# FY_-_OPTO_BOARD_3_GEN.net
KiCad netlist of a schematic drawn in EAGLE
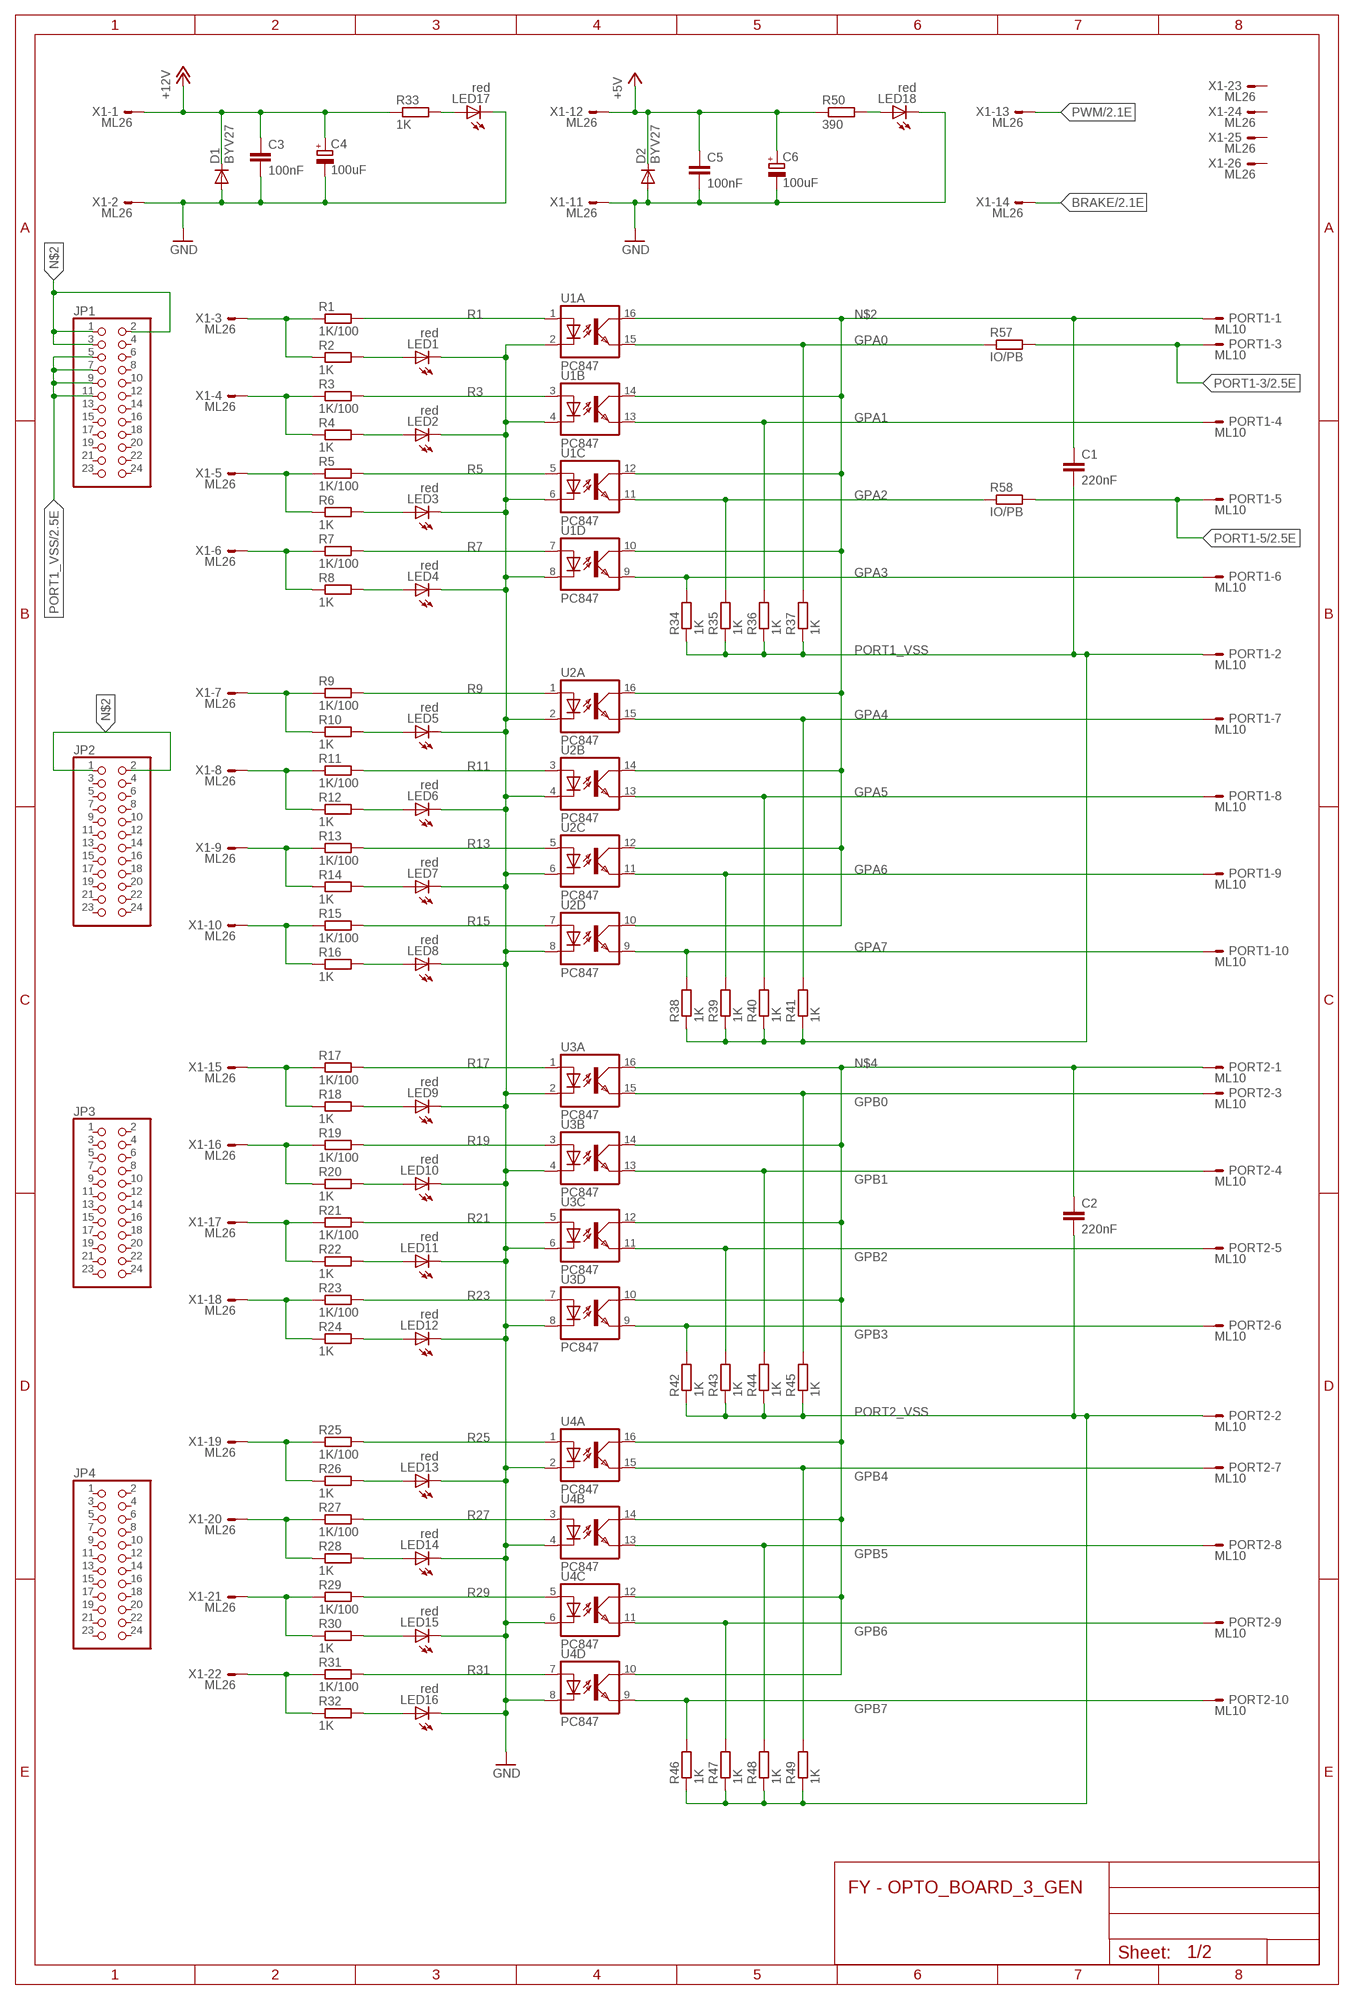
[diagram p0: schematic, sheet 1]
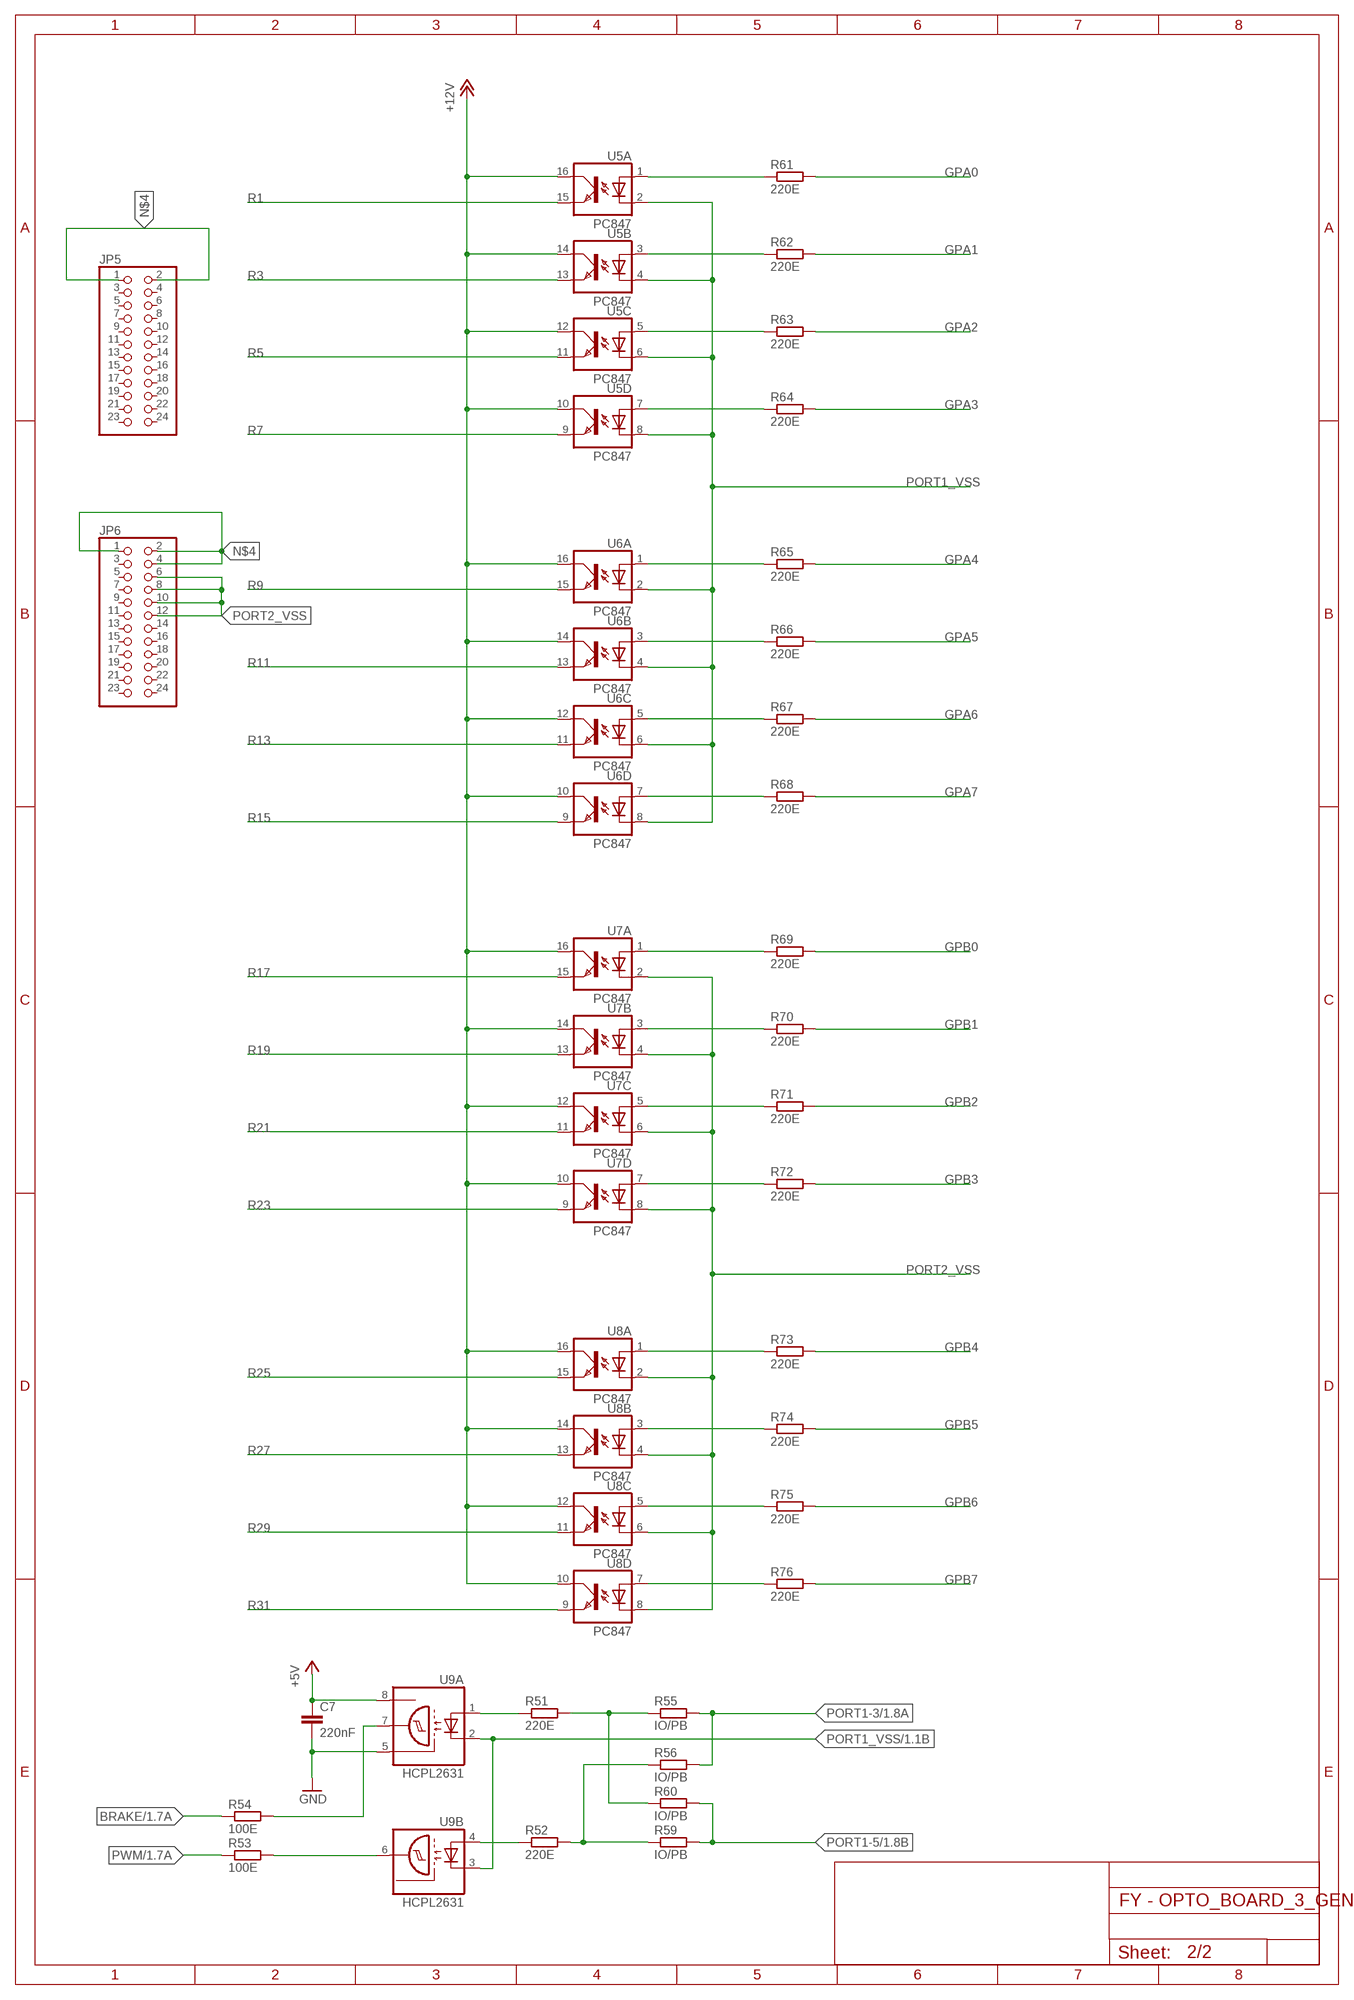
[diagram p1: schematic, sheet 2]

(export (version "E")
  (design (tool "Eeschema 10.0.6"))
  (components
    (comp (ref "C1")
      (value "220nF")
      (footprint "eagle-import:C050-025X075")
      (libsource (lib "eagle-import") (part "C-EU050-025X075"))
    )
    (comp (ref "C2")
      (value "220nF")
      (footprint "eagle-import:C050-025X075")
      (libsource (lib "eagle-import") (part "C-EU050-025X075"))
    )
    (comp (ref "C3")
      (value "100nF")
      (footprint "eagle-import:C050-025X075")
      (libsource (lib "eagle-import") (part "C-EU050-025X075"))
    )
    (comp (ref "C4")
      (value "100uF")
      (footprint "eagle-import:E5-8,5")
      (libsource (lib "eagle-import") (part "CPOL-EUE5-8.5"))
    )
    (comp (ref "C5")
      (value "100nF")
      (footprint "eagle-import:C050-025X075")
      (libsource (lib "eagle-import") (part "C-EU050-025X075"))
    )
    (comp (ref "C6")
      (value "100uF")
      (footprint "eagle-import:E5-8,5")
      (libsource (lib "eagle-import") (part "CPOL-EUE5-8.5"))
    )
    (comp (ref "D1")
      (value "BYV27")
      (footprint "eagle-import:SOD57-10")
      (libsource (lib "eagle-import") (part "BYV27"))
    )
    (comp (ref "D2")
      (value "BYV27")
      (footprint "eagle-import:SOD57-10")
      (libsource (lib "eagle-import") (part "BYV27"))
    )
    (comp (ref "JP1")
      (value "PINHD-2X12")
      (footprint "eagle-import:2X12")
      (libsource (lib "eagle-import") (part "PINHD-2X12"))
    )
    (comp (ref "JP2")
      (value "PINHD-2X12")
      (footprint "eagle-import:2X12")
      (libsource (lib "eagle-import") (part "PINHD-2X12"))
    )
    (comp (ref "JP3")
      (value "PINHD-2X12")
      (footprint "eagle-import:2X12")
      (libsource (lib "eagle-import") (part "PINHD-2X12"))
    )
    (comp (ref "JP4")
      (value "PINHD-2X12")
      (footprint "eagle-import:2X12")
      (libsource (lib "eagle-import") (part "PINHD-2X12"))
    )
    (comp (ref "LED1")
      (value "red")
      (footprint "eagle-import:LED3MM")
      (libsource (lib "eagle-import") (part "LED3MM"))
    )
    (comp (ref "LED2")
      (value "red")
      (footprint "eagle-import:LED3MM")
      (libsource (lib "eagle-import") (part "LED3MM"))
    )
    (comp (ref "LED3")
      (value "red")
      (footprint "eagle-import:LED3MM")
      (libsource (lib "eagle-import") (part "LED3MM"))
    )
    (comp (ref "LED4")
      (value "red")
      (footprint "eagle-import:LED3MM")
      (libsource (lib "eagle-import") (part "LED3MM"))
    )
    (comp (ref "LED5")
      (value "red")
      (footprint "eagle-import:LED3MM")
      (libsource (lib "eagle-import") (part "LED3MM"))
    )
    (comp (ref "LED6")
      (value "red")
      (footprint "eagle-import:LED3MM")
      (libsource (lib "eagle-import") (part "LED3MM"))
    )
    (comp (ref "LED7")
      (value "red")
      (footprint "eagle-import:LED3MM")
      (libsource (lib "eagle-import") (part "LED3MM"))
    )
    (comp (ref "LED8")
      (value "red")
      (footprint "eagle-import:LED3MM")
      (libsource (lib "eagle-import") (part "LED3MM"))
    )
    (comp (ref "LED9")
      (value "red")
      (footprint "eagle-import:LED3MM")
      (libsource (lib "eagle-import") (part "LED3MM"))
    )
    (comp (ref "LED10")
      (value "red")
      (footprint "eagle-import:LED3MM")
      (libsource (lib "eagle-import") (part "LED3MM"))
    )
    (comp (ref "LED11")
      (value "red")
      (footprint "eagle-import:LED3MM")
      (libsource (lib "eagle-import") (part "LED3MM"))
    )
    (comp (ref "LED12")
      (value "red")
      (footprint "eagle-import:LED3MM")
      (libsource (lib "eagle-import") (part "LED3MM"))
    )
    (comp (ref "LED13")
      (value "red")
      (footprint "eagle-import:LED3MM")
      (libsource (lib "eagle-import") (part "LED3MM"))
    )
    (comp (ref "LED14")
      (value "red")
      (footprint "eagle-import:LED3MM")
      (libsource (lib "eagle-import") (part "LED3MM"))
    )
    (comp (ref "LED15")
      (value "red")
      (footprint "eagle-import:LED3MM")
      (libsource (lib "eagle-import") (part "LED3MM"))
    )
    (comp (ref "LED16")
      (value "red")
      (footprint "eagle-import:LED3MM")
      (libsource (lib "eagle-import") (part "LED3MM"))
    )
    (comp (ref "LED17")
      (value "red")
      (footprint "eagle-import:LED3MM")
      (libsource (lib "eagle-import") (part "LED3MM"))
    )
    (comp (ref "LED18")
      (value "red")
      (footprint "eagle-import:LED3MM")
      (libsource (lib "eagle-import") (part "LED3MM"))
    )
    (comp (ref "PORT1")
      (value "ML10")
      (footprint "eagle-import:ML10")
      (libsource (lib "eagle-import") (part "ML10?E"))
    )
    (comp (ref "PORT2")
      (value "ML10")
      (footprint "eagle-import:ML10")
      (libsource (lib "eagle-import") (part "ML10?E"))
    )
    (comp (ref "R1")
      (value "1K/100")
      (footprint "eagle-import:0207_10")
      (libsource (lib "eagle-import") (part "R-EU_0207/10"))
    )
    (comp (ref "R2")
      (value "1K")
      (footprint "eagle-import:0207_10")
      (libsource (lib "eagle-import") (part "R-EU_0207/10"))
    )
    (comp (ref "R3")
      (value "1K/100")
      (footprint "eagle-import:0207_10")
      (libsource (lib "eagle-import") (part "R-EU_0207/10"))
    )
    (comp (ref "R4")
      (value "1K")
      (footprint "eagle-import:0207_10")
      (libsource (lib "eagle-import") (part "R-EU_0207/10"))
    )
    (comp (ref "R5")
      (value "1K/100")
      (footprint "eagle-import:0207_10")
      (libsource (lib "eagle-import") (part "R-EU_0207/10"))
    )
    (comp (ref "R6")
      (value "1K")
      (footprint "eagle-import:0207_10")
      (libsource (lib "eagle-import") (part "R-EU_0207/10"))
    )
    (comp (ref "R7")
      (value "1K/100")
      (footprint "eagle-import:0207_10")
      (libsource (lib "eagle-import") (part "R-EU_0207/10"))
    )
    (comp (ref "R8")
      (value "1K")
      (footprint "eagle-import:0207_10")
      (libsource (lib "eagle-import") (part "R-EU_0207/10"))
    )
    (comp (ref "R9")
      (value "1K/100")
      (footprint "eagle-import:0207_10")
      (libsource (lib "eagle-import") (part "R-EU_0207/10"))
    )
    (comp (ref "R10")
      (value "1K")
      (footprint "eagle-import:0207_10")
      (libsource (lib "eagle-import") (part "R-EU_0207/10"))
    )
    (comp (ref "R11")
      (value "1K/100")
      (footprint "eagle-import:0207_10")
      (libsource (lib "eagle-import") (part "R-EU_0207/10"))
    )
    (comp (ref "R12")
      (value "1K")
      (footprint "eagle-import:0207_10")
      (libsource (lib "eagle-import") (part "R-EU_0207/10"))
    )
    (comp (ref "R13")
      (value "1K/100")
      (footprint "eagle-import:0207_10")
      (libsource (lib "eagle-import") (part "R-EU_0207/10"))
    )
    (comp (ref "R14")
      (value "1K")
      (footprint "eagle-import:0207_10")
      (libsource (lib "eagle-import") (part "R-EU_0207/10"))
    )
    (comp (ref "R15")
      (value "1K/100")
      (footprint "eagle-import:0207_10")
      (libsource (lib "eagle-import") (part "R-EU_0207/10"))
    )
    (comp (ref "R16")
      (value "1K")
      (footprint "eagle-import:0207_10")
      (libsource (lib "eagle-import") (part "R-EU_0207/10"))
    )
    (comp (ref "R17")
      (value "1K/100")
      (footprint "eagle-import:0207_10")
      (libsource (lib "eagle-import") (part "R-EU_0207/10"))
    )
    (comp (ref "R18")
      (value "1K")
      (footprint "eagle-import:0207_10")
      (libsource (lib "eagle-import") (part "R-EU_0207/10"))
    )
    (comp (ref "R19")
      (value "1K/100")
      (footprint "eagle-import:0207_10")
      (libsource (lib "eagle-import") (part "R-EU_0207/10"))
    )
    (comp (ref "R20")
      (value "1K")
      (footprint "eagle-import:0207_10")
      (libsource (lib "eagle-import") (part "R-EU_0207/10"))
    )
    (comp (ref "R21")
      (value "1K/100")
      (footprint "eagle-import:0207_10")
      (libsource (lib "eagle-import") (part "R-EU_0207/10"))
    )
    (comp (ref "R22")
      (value "1K")
      (footprint "eagle-import:0207_10")
      (libsource (lib "eagle-import") (part "R-EU_0207/10"))
    )
    (comp (ref "R23")
      (value "1K/100")
      (footprint "eagle-import:0207_10")
      (libsource (lib "eagle-import") (part "R-EU_0207/10"))
    )
    (comp (ref "R24")
      (value "1K")
      (footprint "eagle-import:0207_10")
      (libsource (lib "eagle-import") (part "R-EU_0207/10"))
    )
    (comp (ref "R25")
      (value "1K/100")
      (footprint "eagle-import:0207_10")
      (libsource (lib "eagle-import") (part "R-EU_0207/10"))
    )
    (comp (ref "R26")
      (value "1K")
      (footprint "eagle-import:0207_10")
      (libsource (lib "eagle-import") (part "R-EU_0207/10"))
    )
    (comp (ref "R27")
      (value "1K/100")
      (footprint "eagle-import:0207_10")
      (libsource (lib "eagle-import") (part "R-EU_0207/10"))
    )
    (comp (ref "R28")
      (value "1K")
      (footprint "eagle-import:0207_10")
      (libsource (lib "eagle-import") (part "R-EU_0207/10"))
    )
    (comp (ref "R29")
      (value "1K/100")
      (footprint "eagle-import:0207_10")
      (libsource (lib "eagle-import") (part "R-EU_0207/10"))
    )
    (comp (ref "R30")
      (value "1K")
      (footprint "eagle-import:0207_10")
      (libsource (lib "eagle-import") (part "R-EU_0207/10"))
    )
    (comp (ref "R31")
      (value "1K/100")
      (footprint "eagle-import:0207_10")
      (libsource (lib "eagle-import") (part "R-EU_0207/10"))
    )
    (comp (ref "R32")
      (value "1K")
      (footprint "eagle-import:0207_10")
      (libsource (lib "eagle-import") (part "R-EU_0207/10"))
    )
    (comp (ref "R33")
      (value "1K")
      (footprint "eagle-import:0207_10")
      (libsource (lib "eagle-import") (part "R-EU_0207/10"))
    )
    (comp (ref "R34")
      (value "1K")
      (footprint "eagle-import:0207_10")
      (libsource (lib "eagle-import") (part "R-EU_0207/10"))
    )
    (comp (ref "R35")
      (value "1K")
      (footprint "eagle-import:0207_10")
      (libsource (lib "eagle-import") (part "R-EU_0207/10"))
    )
    (comp (ref "R36")
      (value "1K")
      (footprint "eagle-import:0207_10")
      (libsource (lib "eagle-import") (part "R-EU_0207/10"))
    )
    (comp (ref "R37")
      (value "1K")
      (footprint "eagle-import:0207_10")
      (libsource (lib "eagle-import") (part "R-EU_0207/10"))
    )
    (comp (ref "R38")
      (value "1K")
      (footprint "eagle-import:0207_10")
      (libsource (lib "eagle-import") (part "R-EU_0207/10"))
    )
    (comp (ref "R39")
      (value "1K")
      (footprint "eagle-import:0207_10")
      (libsource (lib "eagle-import") (part "R-EU_0207/10"))
    )
    (comp (ref "R40")
      (value "1K")
      (footprint "eagle-import:0207_10")
      (libsource (lib "eagle-import") (part "R-EU_0207/10"))
    )
    (comp (ref "R41")
      (value "1K")
      (footprint "eagle-import:0207_10")
      (libsource (lib "eagle-import") (part "R-EU_0207/10"))
    )
    (comp (ref "R42")
      (value "1K")
      (footprint "eagle-import:0207_10")
      (libsource (lib "eagle-import") (part "R-EU_0207/10"))
    )
    (comp (ref "R43")
      (value "1K")
      (footprint "eagle-import:0207_10")
      (libsource (lib "eagle-import") (part "R-EU_0207/10"))
    )
    (comp (ref "R44")
      (value "1K")
      (footprint "eagle-import:0207_10")
      (libsource (lib "eagle-import") (part "R-EU_0207/10"))
    )
    (comp (ref "R45")
      (value "1K")
      (footprint "eagle-import:0207_10")
      (libsource (lib "eagle-import") (part "R-EU_0207/10"))
    )
    (comp (ref "R46")
      (value "1K")
      (footprint "eagle-import:0207_10")
      (libsource (lib "eagle-import") (part "R-EU_0207/10"))
    )
    (comp (ref "R47")
      (value "1K")
      (footprint "eagle-import:0207_10")
      (libsource (lib "eagle-import") (part "R-EU_0207/10"))
    )
    (comp (ref "R48")
      (value "1K")
      (footprint "eagle-import:0207_10")
      (libsource (lib "eagle-import") (part "R-EU_0207/10"))
    )
    (comp (ref "R49")
      (value "1K")
      (footprint "eagle-import:0207_10")
      (libsource (lib "eagle-import") (part "R-EU_0207/10"))
    )
    (comp (ref "R50")
      (value "390")
      (footprint "eagle-import:0207_10")
      (libsource (lib "eagle-import") (part "R-EU_0207/10"))
    )
    (comp (ref "R57")
      (value "IO/PB")
      (footprint "eagle-import:0204V")
      (libsource (lib "eagle-import") (part "R-EU_0204/2V"))
    )
    (comp (ref "R58")
      (value "IO/PB")
      (footprint "eagle-import:0204V")
      (libsource (lib "eagle-import") (part "R-EU_0204/2V"))
    )
    (comp (ref "U1")
      (value "PC847")
      (footprint "eagle-import:DIL16")
      (libsource (lib "eagle-import") (part "PC847"))
    )
    (comp (ref "U2")
      (value "PC847")
      (footprint "eagle-import:DIL16")
      (libsource (lib "eagle-import") (part "PC847"))
    )
    (comp (ref "U3")
      (value "PC847")
      (footprint "eagle-import:DIL16")
      (libsource (lib "eagle-import") (part "PC847"))
    )
    (comp (ref "U4")
      (value "PC847")
      (footprint "eagle-import:DIL16")
      (libsource (lib "eagle-import") (part "PC847"))
    )
    (comp (ref "X1")
      (value "ML26")
      (footprint "eagle-import:ML26")
      (libsource (lib "eagle-import") (part "ML26?E"))
    )
    (comp (ref "C7")
      (value "220nF")
      (footprint "eagle-import:C050-025X075")
      (libsource (lib "eagle-import") (part "C-EU050-025X075"))
    )
    (comp (ref "JP5")
      (value "PINHD-2X12")
      (footprint "eagle-import:2X12")
      (libsource (lib "eagle-import") (part "PINHD-2X12"))
    )
    (comp (ref "JP6")
      (value "PINHD-2X12")
      (footprint "eagle-import:2X12")
      (libsource (lib "eagle-import") (part "PINHD-2X12"))
    )
    (comp (ref "R51")
      (value "220E")
      (footprint "eagle-import:0207_10")
      (libsource (lib "eagle-import") (part "R-EU_0207/10"))
    )
    (comp (ref "R52")
      (value "220E")
      (footprint "eagle-import:0207_10")
      (libsource (lib "eagle-import") (part "R-EU_0207/10"))
    )
    (comp (ref "R53")
      (value "100E")
      (footprint "eagle-import:0207_10")
      (libsource (lib "eagle-import") (part "R-EU_0207/10"))
    )
    (comp (ref "R54")
      (value "100E")
      (footprint "eagle-import:0207_10")
      (libsource (lib "eagle-import") (part "R-EU_0207/10"))
    )
    (comp (ref "R55")
      (value "IO/PB")
      (footprint "eagle-import:0204V")
      (libsource (lib "eagle-import") (part "R-EU_0204/2V"))
    )
    (comp (ref "R56")
      (value "IO/PB")
      (footprint "eagle-import:0204V")
      (libsource (lib "eagle-import") (part "R-EU_0204/2V"))
    )
    (comp (ref "R59")
      (value "IO/PB")
      (footprint "eagle-import:0204V")
      (libsource (lib "eagle-import") (part "R-EU_0204/2V"))
    )
    (comp (ref "R60")
      (value "IO/PB")
      (footprint "eagle-import:0204V")
      (libsource (lib "eagle-import") (part "R-EU_0204/2V"))
    )
    (comp (ref "R61")
      (value "220E")
      (footprint "eagle-import:0207_10")
      (libsource (lib "eagle-import") (part "R-EU_0207/10"))
    )
    (comp (ref "R62")
      (value "220E")
      (footprint "eagle-import:0207_10")
      (libsource (lib "eagle-import") (part "R-EU_0207/10"))
    )
    (comp (ref "R63")
      (value "220E")
      (footprint "eagle-import:0207_10")
      (libsource (lib "eagle-import") (part "R-EU_0207/10"))
    )
    (comp (ref "R64")
      (value "220E")
      (footprint "eagle-import:0207_10")
      (libsource (lib "eagle-import") (part "R-EU_0207/10"))
    )
    (comp (ref "R65")
      (value "220E")
      (footprint "eagle-import:0207_10")
      (libsource (lib "eagle-import") (part "R-EU_0207/10"))
    )
    (comp (ref "R66")
      (value "220E")
      (footprint "eagle-import:0207_10")
      (libsource (lib "eagle-import") (part "R-EU_0207/10"))
    )
    (comp (ref "R67")
      (value "220E")
      (footprint "eagle-import:0207_10")
      (libsource (lib "eagle-import") (part "R-EU_0207/10"))
    )
    (comp (ref "R68")
      (value "220E")
      (footprint "eagle-import:0207_10")
      (libsource (lib "eagle-import") (part "R-EU_0207/10"))
    )
    (comp (ref "R69")
      (value "220E")
      (footprint "eagle-import:0207_10")
      (libsource (lib "eagle-import") (part "R-EU_0207/10"))
    )
    (comp (ref "R70")
      (value "220E")
      (footprint "eagle-import:0207_10")
      (libsource (lib "eagle-import") (part "R-EU_0207/10"))
    )
    (comp (ref "R71")
      (value "220E")
      (footprint "eagle-import:0207_10")
      (libsource (lib "eagle-import") (part "R-EU_0207/10"))
    )
    (comp (ref "R72")
      (value "220E")
      (footprint "eagle-import:0207_10")
      (libsource (lib "eagle-import") (part "R-EU_0207/10"))
    )
    (comp (ref "R73")
      (value "220E")
      (footprint "eagle-import:0207_10")
      (libsource (lib "eagle-import") (part "R-EU_0207/10"))
    )
    (comp (ref "R74")
      (value "220E")
      (footprint "eagle-import:0207_10")
      (libsource (lib "eagle-import") (part "R-EU_0207/10"))
    )
    (comp (ref "R75")
      (value "220E")
      (footprint "eagle-import:0207_10")
      (libsource (lib "eagle-import") (part "R-EU_0207/10"))
    )
    (comp (ref "R76")
      (value "220E")
      (footprint "eagle-import:0207_10")
      (libsource (lib "eagle-import") (part "R-EU_0207/10"))
    )
    (comp (ref "U5")
      (value "PC847")
      (footprint "eagle-import:DIL16")
      (libsource (lib "eagle-import") (part "PC847"))
    )
    (comp (ref "U6")
      (value "PC847")
      (footprint "eagle-import:DIL16")
      (libsource (lib "eagle-import") (part "PC847"))
    )
    (comp (ref "U7")
      (value "PC847")
      (footprint "eagle-import:DIL16")
      (libsource (lib "eagle-import") (part "PC847"))
    )
    (comp (ref "U8")
      (value "PC847")
      (footprint "eagle-import:DIL16")
      (libsource (lib "eagle-import") (part "PC847"))
    )
    (comp (ref "U9")
      (value "HCPL2631")
      (footprint "eagle-import:DIL08")
      (fields (field (name "MF") "AGILENT TECHNOLOGIES") (field (name "MPN") "HCPL-2231-000E"))
      (libsource (lib "eagle-import") (part "HCPL2231"))
    )
  )
  (nets
    (net (code "1") (name "+5V") (class "Default")
      (node (ref "C5") (pin "1") (pinfunction "1_1") (pintype "passive"))
      (node (ref "C6") (pin "+") (pinfunction "+_+") (pintype "passive"))
      (node (ref "C7") (pin "1") (pinfunction "1_1") (pintype "passive"))
      (node (ref "D2") (pin "C") (pinfunction "C_C") (pintype "passive"))
      (node (ref "R50") (pin "1") (pinfunction "1_1") (pintype "passive"))
      (node (ref "U9") (pin "8") (pinfunction "VCC_8") (pintype "passive"))
      (node (ref "X1") (pin "12") (pinfunction "S_12") (pintype "passive"))
    )
    (net (code "2") (name "+12V") (class "Default")
      (node (ref "C3") (pin "1") (pinfunction "1_1") (pintype "passive"))
      (node (ref "C4") (pin "+") (pinfunction "+_+") (pintype "passive"))
      (node (ref "D1") (pin "C") (pinfunction "C_C") (pintype "passive"))
      (node (ref "R33") (pin "1") (pinfunction "1_1") (pintype "passive"))
      (node (ref "U5") (pin "10") (pinfunction "COL_10") (pintype "passive"))
      (node (ref "U5") (pin "12") (pinfunction "COL_12") (pintype "passive"))
      (node (ref "U5") (pin "14") (pinfunction "COL_14") (pintype "passive"))
      (node (ref "U5") (pin "16") (pinfunction "COL_16") (pintype "passive"))
      (node (ref "U6") (pin "10") (pinfunction "COL_10") (pintype "passive"))
      (node (ref "U6") (pin "12") (pinfunction "COL_12") (pintype "passive"))
      (node (ref "U6") (pin "14") (pinfunction "COL_14") (pintype "passive"))
      (node (ref "U6") (pin "16") (pinfunction "COL_16") (pintype "passive"))
      (node (ref "U7") (pin "10") (pinfunction "COL_10") (pintype "passive"))
      (node (ref "U7") (pin "12") (pinfunction "COL_12") (pintype "passive"))
      (node (ref "U7") (pin "14") (pinfunction "COL_14") (pintype "passive"))
      (node (ref "U7") (pin "16") (pinfunction "COL_16") (pintype "passive"))
      (node (ref "U8") (pin "10") (pinfunction "COL_10") (pintype "passive"))
      (node (ref "U8") (pin "12") (pinfunction "COL_12") (pintype "passive"))
      (node (ref "U8") (pin "14") (pinfunction "COL_14") (pintype "passive"))
      (node (ref "U8") (pin "16") (pinfunction "COL_16") (pintype "passive"))
      (node (ref "X1") (pin "1") (pinfunction "S_1") (pintype "passive"))
    )
    (net (code "3") (name "BRAKE") (class "Default")
      (node (ref "R54") (pin "1") (pinfunction "1_1") (pintype "passive"))
      (node (ref "X1") (pin "14") (pinfunction "S_14") (pintype "passive"))
    )
    (net (code "4") (name "GND") (class "Default")
      (node (ref "C3") (pin "2") (pinfunction "2_2") (pintype "passive"))
      (node (ref "C4") (pin "-") (pinfunction "-_-") (pintype "passive"))
      (node (ref "C5") (pin "2") (pinfunction "2_2") (pintype "passive"))
      (node (ref "C6") (pin "-") (pinfunction "-_-") (pintype "passive"))
      (node (ref "C7") (pin "2") (pinfunction "2_2") (pintype "passive"))
      (node (ref "D1") (pin "A") (pinfunction "A_A") (pintype "passive"))
      (node (ref "D2") (pin "A") (pinfunction "A_A") (pintype "passive"))
      (node (ref "LED1") (pin "K") (pinfunction "C_K") (pintype "passive"))
      (node (ref "LED10") (pin "K") (pinfunction "C_K") (pintype "passive"))
      (node (ref "LED11") (pin "K") (pinfunction "C_K") (pintype "passive"))
      (node (ref "LED12") (pin "K") (pinfunction "C_K") (pintype "passive"))
      (node (ref "LED13") (pin "K") (pinfunction "C_K") (pintype "passive"))
      (node (ref "LED14") (pin "K") (pinfunction "C_K") (pintype "passive"))
      (node (ref "LED15") (pin "K") (pinfunction "C_K") (pintype "passive"))
      (node (ref "LED16") (pin "K") (pinfunction "C_K") (pintype "passive"))
      (node (ref "LED17") (pin "K") (pinfunction "C_K") (pintype "passive"))
      (node (ref "LED18") (pin "K") (pinfunction "C_K") (pintype "passive"))
      (node (ref "LED2") (pin "K") (pinfunction "C_K") (pintype "passive"))
      (node (ref "LED3") (pin "K") (pinfunction "C_K") (pintype "passive"))
      (node (ref "LED4") (pin "K") (pinfunction "C_K") (pintype "passive"))
      (node (ref "LED5") (pin "K") (pinfunction "C_K") (pintype "passive"))
      (node (ref "LED6") (pin "K") (pinfunction "C_K") (pintype "passive"))
      (node (ref "LED7") (pin "K") (pinfunction "C_K") (pintype "passive"))
      (node (ref "LED8") (pin "K") (pinfunction "C_K") (pintype "passive"))
      (node (ref "LED9") (pin "K") (pinfunction "C_K") (pintype "passive"))
      (node (ref "U1") (pin "2") (pinfunction "C_2") (pintype "passive"))
      (node (ref "U1") (pin "4") (pinfunction "C_4") (pintype "passive"))
      (node (ref "U1") (pin "6") (pinfunction "C_6") (pintype "passive"))
      (node (ref "U1") (pin "8") (pinfunction "C_8") (pintype "passive"))
      (node (ref "U2") (pin "2") (pinfunction "C_2") (pintype "passive"))
      (node (ref "U2") (pin "4") (pinfunction "C_4") (pintype "passive"))
      (node (ref "U2") (pin "6") (pinfunction "C_6") (pintype "passive"))
      (node (ref "U2") (pin "8") (pinfunction "C_8") (pintype "passive"))
      (node (ref "U3") (pin "2") (pinfunction "C_2") (pintype "passive"))
      (node (ref "U3") (pin "4") (pinfunction "C_4") (pintype "passive"))
      (node (ref "U3") (pin "6") (pinfunction "C_6") (pintype "passive"))
      (node (ref "U3") (pin "8") (pinfunction "C_8") (pintype "passive"))
      (node (ref "U4") (pin "2") (pinfunction "C_2") (pintype "passive"))
      (node (ref "U4") (pin "4") (pinfunction "C_4") (pintype "passive"))
      (node (ref "U4") (pin "6") (pinfunction "C_6") (pintype "passive"))
      (node (ref "U4") (pin "8") (pinfunction "C_8") (pintype "passive"))
      (node (ref "U9") (pin "5") (pinfunction "GND_5") (pintype "passive"))
      (node (ref "X1") (pin "11") (pinfunction "S_11") (pintype "passive"))
      (node (ref "X1") (pin "2") (pinfunction "S_2") (pintype "passive"))
    )
    (net (code "5") (name "GPA0") (class "Default")
      (node (ref "R37") (pin "2") (pinfunction "2_2") (pintype "passive"))
      (node (ref "R57") (pin "1") (pinfunction "1_1") (pintype "passive"))
      (node (ref "R61") (pin "2") (pinfunction "2_2") (pintype "passive"))
      (node (ref "U1") (pin "15") (pinfunction "EMIT_15") (pintype "passive"))
    )
    (net (code "6") (name "GPA1") (class "Default")
      (node (ref "PORT1") (pin "4") (pinfunction "S_4") (pintype "passive"))
      (node (ref "R36") (pin "2") (pinfunction "2_2") (pintype "passive"))
      (node (ref "R62") (pin "2") (pinfunction "2_2") (pintype "passive"))
      (node (ref "U1") (pin "13") (pinfunction "EMIT_13") (pintype "passive"))
    )
    (net (code "7") (name "GPA2") (class "Default")
      (node (ref "R35") (pin "2") (pinfunction "2_2") (pintype "passive"))
      (node (ref "R58") (pin "1") (pinfunction "1_1") (pintype "passive"))
      (node (ref "R63") (pin "2") (pinfunction "2_2") (pintype "passive"))
      (node (ref "U1") (pin "11") (pinfunction "EMIT_11") (pintype "passive"))
    )
    (net (code "8") (name "GPA3") (class "Default")
      (node (ref "PORT1") (pin "6") (pinfunction "S_6") (pintype "passive"))
      (node (ref "R34") (pin "2") (pinfunction "2_2") (pintype "passive"))
      (node (ref "R64") (pin "2") (pinfunction "2_2") (pintype "passive"))
      (node (ref "U1") (pin "9") (pinfunction "EMIT_9") (pintype "passive"))
    )
    (net (code "9") (name "GPA4") (class "Default")
      (node (ref "PORT1") (pin "7") (pinfunction "S_7") (pintype "passive"))
      (node (ref "R41") (pin "2") (pinfunction "2_2") (pintype "passive"))
      (node (ref "R65") (pin "2") (pinfunction "2_2") (pintype "passive"))
      (node (ref "U2") (pin "15") (pinfunction "EMIT_15") (pintype "passive"))
    )
    (net (code "10") (name "GPA5") (class "Default")
      (node (ref "PORT1") (pin "8") (pinfunction "S_8") (pintype "passive"))
      (node (ref "R40") (pin "2") (pinfunction "2_2") (pintype "passive"))
      (node (ref "R66") (pin "2") (pinfunction "2_2") (pintype "passive"))
      (node (ref "U2") (pin "13") (pinfunction "EMIT_13") (pintype "passive"))
    )
    (net (code "11") (name "GPA6") (class "Default")
      (node (ref "PORT1") (pin "9") (pinfunction "S_9") (pintype "passive"))
      (node (ref "R39") (pin "2") (pinfunction "2_2") (pintype "passive"))
      (node (ref "R67") (pin "2") (pinfunction "2_2") (pintype "passive"))
      (node (ref "U2") (pin "11") (pinfunction "EMIT_11") (pintype "passive"))
    )
    (net (code "12") (name "GPA7") (class "Default")
      (node (ref "PORT1") (pin "10") (pinfunction "S_10") (pintype "passive"))
      (node (ref "R38") (pin "2") (pinfunction "2_2") (pintype "passive"))
      (node (ref "R68") (pin "2") (pinfunction "2_2") (pintype "passive"))
      (node (ref "U2") (pin "9") (pinfunction "EMIT_9") (pintype "passive"))
    )
    (net (code "13") (name "GPB0") (class "Default")
      (node (ref "PORT2") (pin "3") (pinfunction "S_3") (pintype "passive"))
      (node (ref "R45") (pin "2") (pinfunction "2_2") (pintype "passive"))
      (node (ref "R69") (pin "2") (pinfunction "2_2") (pintype "passive"))
      (node (ref "U3") (pin "15") (pinfunction "EMIT_15") (pintype "passive"))
    )
    (net (code "14") (name "GPB1") (class "Default")
      (node (ref "PORT2") (pin "4") (pinfunction "S_4") (pintype "passive"))
      (node (ref "R44") (pin "2") (pinfunction "2_2") (pintype "passive"))
      (node (ref "R70") (pin "2") (pinfunction "2_2") (pintype "passive"))
      (node (ref "U3") (pin "13") (pinfunction "EMIT_13") (pintype "passive"))
    )
    (net (code "15") (name "GPB2") (class "Default")
      (node (ref "PORT2") (pin "5") (pinfunction "S_5") (pintype "passive"))
      (node (ref "R43") (pin "2") (pinfunction "2_2") (pintype "passive"))
      (node (ref "R71") (pin "2") (pinfunction "2_2") (pintype "passive"))
      (node (ref "U3") (pin "11") (pinfunction "EMIT_11") (pintype "passive"))
    )
    (net (code "16") (name "GPB3") (class "Default")
      (node (ref "PORT2") (pin "6") (pinfunction "S_6") (pintype "passive"))
      (node (ref "R42") (pin "2") (pinfunction "2_2") (pintype "passive"))
      (node (ref "R72") (pin "2") (pinfunction "2_2") (pintype "passive"))
      (node (ref "U3") (pin "9") (pinfunction "EMIT_9") (pintype "passive"))
    )
    (net (code "17") (name "GPB4") (class "Default")
      (node (ref "PORT2") (pin "7") (pinfunction "S_7") (pintype "passive"))
      (node (ref "R49") (pin "2") (pinfunction "2_2") (pintype "passive"))
      (node (ref "R73") (pin "2") (pinfunction "2_2") (pintype "passive"))
      (node (ref "U4") (pin "15") (pinfunction "EMIT_15") (pintype "passive"))
    )
    (net (code "18") (name "GPB5") (class "Default")
      (node (ref "PORT2") (pin "8") (pinfunction "S_8") (pintype "passive"))
      (node (ref "R48") (pin "2") (pinfunction "2_2") (pintype "passive"))
      (node (ref "R74") (pin "2") (pinfunction "2_2") (pintype "passive"))
      (node (ref "U4") (pin "13") (pinfunction "EMIT_13") (pintype "passive"))
    )
    (net (code "19") (name "GPB6") (class "Default")
      (node (ref "PORT2") (pin "9") (pinfunction "S_9") (pintype "passive"))
      (node (ref "R47") (pin "2") (pinfunction "2_2") (pintype "passive"))
      (node (ref "R75") (pin "2") (pinfunction "2_2") (pintype "passive"))
      (node (ref "U4") (pin "11") (pinfunction "EMIT_11") (pintype "passive"))
    )
    (net (code "20") (name "GPB7") (class "Default")
      (node (ref "PORT2") (pin "10") (pinfunction "S_10") (pintype "passive"))
      (node (ref "R46") (pin "2") (pinfunction "2_2") (pintype "passive"))
      (node (ref "R76") (pin "2") (pinfunction "2_2") (pintype "passive"))
      (node (ref "U4") (pin "9") (pinfunction "EMIT_9") (pintype "passive"))
    )
    (net (code "21") (name "N$2") (class "Default")
      (node (ref "C1") (pin "1") (pinfunction "1_1") (pintype "passive"))
      (node (ref "JP1") (pin "1") (pinfunction "1_1") (pintype "passive"))
      (node (ref "JP1") (pin "2") (pinfunction "2_2") (pintype "passive"))
      (node (ref "JP1") (pin "3") (pinfunction "3_3") (pintype "passive"))
      (node (ref "JP2") (pin "1") (pinfunction "1_1") (pintype "passive"))
      (node (ref "JP2") (pin "2") (pinfunction "2_2") (pintype "passive"))
      (node (ref "PORT1") (pin "1") (pinfunction "S_1") (pintype "passive"))
      (node (ref "U1") (pin "10") (pinfunction "COL_10") (pintype "passive"))
      (node (ref "U1") (pin "12") (pinfunction "COL_12") (pintype "passive"))
      (node (ref "U1") (pin "14") (pinfunction "COL_14") (pintype "passive"))
      (node (ref "U1") (pin "16") (pinfunction "COL_16") (pintype "passive"))
      (node (ref "U2") (pin "10") (pinfunction "COL_10") (pintype "passive"))
      (node (ref "U2") (pin "12") (pinfunction "COL_12") (pintype "passive"))
      (node (ref "U2") (pin "14") (pinfunction "COL_14") (pintype "passive"))
      (node (ref "U2") (pin "16") (pinfunction "COL_16") (pintype "passive"))
    )
    (net (code "22") (name "N$4") (class "Default")
      (node (ref "C2") (pin "1") (pinfunction "1_1") (pintype "passive"))
      (node (ref "JP5") (pin "1") (pinfunction "1_1") (pintype "passive"))
      (node (ref "JP5") (pin "2") (pinfunction "2_2") (pintype "passive"))
      (node (ref "JP6") (pin "1") (pinfunction "1_1") (pintype "passive"))
      (node (ref "JP6") (pin "2") (pinfunction "2_2") (pintype "passive"))
      (node (ref "JP6") (pin "4") (pinfunction "4_4") (pintype "passive"))
      (node (ref "PORT2") (pin "1") (pinfunction "S_1") (pintype "passive"))
      (node (ref "U3") (pin "10") (pinfunction "COL_10") (pintype "passive"))
      (node (ref "U3") (pin "12") (pinfunction "COL_12") (pintype "passive"))
      (node (ref "U3") (pin "14") (pinfunction "COL_14") (pintype "passive"))
      (node (ref "U3") (pin "16") (pinfunction "COL_16") (pintype "passive"))
      (node (ref "U4") (pin "10") (pinfunction "COL_10") (pintype "passive"))
      (node (ref "U4") (pin "12") (pinfunction "COL_12") (pintype "passive"))
      (node (ref "U4") (pin "14") (pinfunction "COL_14") (pintype "passive"))
      (node (ref "U4") (pin "16") (pinfunction "COL_16") (pintype "passive"))
    )
    (net (code "23") (name "Net-(LED1-PadA)") (class "Default")
      (node (ref "LED1") (pin "A") (pinfunction "A_A") (pintype "passive"))
      (node (ref "R2") (pin "2") (pinfunction "2_2") (pintype "passive"))
    )
    (net (code "24") (name "Net-(LED2-PadA)") (class "Default")
      (node (ref "LED2") (pin "A") (pinfunction "A_A") (pintype "passive"))
      (node (ref "R4") (pin "2") (pinfunction "2_2") (pintype "passive"))
    )
    (net (code "25") (name "Net-(LED3-PadA)") (class "Default")
      (node (ref "LED3") (pin "A") (pinfunction "A_A") (pintype "passive"))
      (node (ref "R6") (pin "2") (pinfunction "2_2") (pintype "passive"))
    )
    (net (code "26") (name "Net-(LED4-PadA)") (class "Default")
      (node (ref "LED4") (pin "A") (pinfunction "A_A") (pintype "passive"))
      (node (ref "R8") (pin "2") (pinfunction "2_2") (pintype "passive"))
    )
    (net (code "27") (name "Net-(LED5-PadA)") (class "Default")
      (node (ref "LED5") (pin "A") (pinfunction "A_A") (pintype "passive"))
      (node (ref "R10") (pin "2") (pinfunction "2_2") (pintype "passive"))
    )
    (net (code "28") (name "Net-(LED6-PadA)") (class "Default")
      (node (ref "LED6") (pin "A") (pinfunction "A_A") (pintype "passive"))
      (node (ref "R12") (pin "2") (pinfunction "2_2") (pintype "passive"))
    )
    (net (code "29") (name "Net-(LED7-PadA)") (class "Default")
      (node (ref "LED7") (pin "A") (pinfunction "A_A") (pintype "passive"))
      (node (ref "R14") (pin "2") (pinfunction "2_2") (pintype "passive"))
    )
    (net (code "30") (name "Net-(LED8-PadA)") (class "Default")
      (node (ref "LED8") (pin "A") (pinfunction "A_A") (pintype "passive"))
      (node (ref "R16") (pin "2") (pinfunction "2_2") (pintype "passive"))
    )
    (net (code "31") (name "Net-(LED9-PadA)") (class "Default")
      (node (ref "LED9") (pin "A") (pinfunction "A_A") (pintype "passive"))
      (node (ref "R18") (pin "2") (pinfunction "2_2") (pintype "passive"))
    )
    (net (code "32") (name "Net-(LED10-PadA)") (class "Default")
      (node (ref "LED10") (pin "A") (pinfunction "A_A") (pintype "passive"))
      (node (ref "R20") (pin "2") (pinfunction "2_2") (pintype "passive"))
    )
    (net (code "33") (name "Net-(LED11-PadA)") (class "Default")
      (node (ref "LED11") (pin "A") (pinfunction "A_A") (pintype "passive"))
      (node (ref "R22") (pin "2") (pinfunction "2_2") (pintype "passive"))
    )
    (net (code "34") (name "Net-(LED12-PadA)") (class "Default")
      (node (ref "LED12") (pin "A") (pinfunction "A_A") (pintype "passive"))
      (node (ref "R24") (pin "2") (pinfunction "2_2") (pintype "passive"))
    )
    (net (code "35") (name "Net-(LED13-PadA)") (class "Default")
      (node (ref "LED13") (pin "A") (pinfunction "A_A") (pintype "passive"))
      (node (ref "R26") (pin "2") (pinfunction "2_2") (pintype "passive"))
    )
    (net (code "36") (name "Net-(LED14-PadA)") (class "Default")
      (node (ref "LED14") (pin "A") (pinfunction "A_A") (pintype "passive"))
      (node (ref "R28") (pin "2") (pinfunction "2_2") (pintype "passive"))
    )
    (net (code "37") (name "Net-(LED15-PadA)") (class "Default")
      (node (ref "LED15") (pin "A") (pinfunction "A_A") (pintype "passive"))
      (node (ref "R30") (pin "2") (pinfunction "2_2") (pintype "passive"))
    )
    (net (code "38") (name "Net-(LED16-PadA)") (class "Default")
      (node (ref "LED16") (pin "A") (pinfunction "A_A") (pintype "passive"))
      (node (ref "R32") (pin "2") (pinfunction "2_2") (pintype "passive"))
    )
    (net (code "39") (name "Net-(LED17-PadA)") (class "Default")
      (node (ref "LED17") (pin "A") (pinfunction "A_A") (pintype "passive"))
      (node (ref "R33") (pin "2") (pinfunction "2_2") (pintype "passive"))
    )
    (net (code "40") (name "Net-(LED18-PadA)") (class "Default")
      (node (ref "LED18") (pin "A") (pinfunction "A_A") (pintype "passive"))
      (node (ref "R50") (pin "2") (pinfunction "2_2") (pintype "passive"))
    )
    (net (code "41") (name "Net-(R51-Pad2)") (class "Default")
      (node (ref "R51") (pin "2") (pinfunction "2_2") (pintype "passive"))
      (node (ref "R55") (pin "1") (pinfunction "1_1") (pintype "passive"))
      (node (ref "R60") (pin "1") (pinfunction "1_1") (pintype "passive"))
    )
    (net (code "42") (name "Net-(R52-Pad2)") (class "Default")
      (node (ref "R52") (pin "2") (pinfunction "2_2") (pintype "passive"))
      (node (ref "R56") (pin "1") (pinfunction "1_1") (pintype "passive"))
      (node (ref "R59") (pin "1") (pinfunction "1_1") (pintype "passive"))
    )
    (net (code "43") (name "Net-(U5A-A)") (class "Default")
      (node (ref "R61") (pin "1") (pinfunction "1_1") (pintype "passive"))
      (node (ref "U5") (pin "1") (pinfunction "A_1") (pintype "passive"))
    )
    (net (code "44") (name "Net-(U5B-A)") (class "Default")
      (node (ref "R62") (pin "1") (pinfunction "1_1") (pintype "passive"))
      (node (ref "U5") (pin "3") (pinfunction "A_3") (pintype "passive"))
    )
    (net (code "45") (name "Net-(U5C-A)") (class "Default")
      (node (ref "R63") (pin "1") (pinfunction "1_1") (pintype "passive"))
      (node (ref "U5") (pin "5") (pinfunction "A_5") (pintype "passive"))
    )
    (net (code "46") (name "Net-(U5D-A)") (class "Default")
      (node (ref "R64") (pin "1") (pinfunction "1_1") (pintype "passive"))
      (node (ref "U5") (pin "7") (pinfunction "A_7") (pintype "passive"))
    )
    (net (code "47") (name "Net-(U6A-A)") (class "Default")
      (node (ref "R65") (pin "1") (pinfunction "1_1") (pintype "passive"))
      (node (ref "U6") (pin "1") (pinfunction "A_1") (pintype "passive"))
    )
    (net (code "48") (name "Net-(U6B-A)") (class "Default")
      (node (ref "R66") (pin "1") (pinfunction "1_1") (pintype "passive"))
      (node (ref "U6") (pin "3") (pinfunction "A_3") (pintype "passive"))
    )
    (net (code "49") (name "Net-(U6C-A)") (class "Default")
      (node (ref "R67") (pin "1") (pinfunction "1_1") (pintype "passive"))
      (node (ref "U6") (pin "5") (pinfunction "A_5") (pintype "passive"))
    )
    (net (code "50") (name "Net-(U6D-A)") (class "Default")
      (node (ref "R68") (pin "1") (pinfunction "1_1") (pintype "passive"))
      (node (ref "U6") (pin "7") (pinfunction "A_7") (pintype "passive"))
    )
    (net (code "51") (name "Net-(U7A-A)") (class "Default")
      (node (ref "R69") (pin "1") (pinfunction "1_1") (pintype "passive"))
      (node (ref "U7") (pin "1") (pinfunction "A_1") (pintype "passive"))
    )
    (net (code "52") (name "Net-(U7B-A)") (class "Default")
      (node (ref "R70") (pin "1") (pinfunction "1_1") (pintype "passive"))
      (node (ref "U7") (pin "3") (pinfunction "A_3") (pintype "passive"))
    )
    (net (code "53") (name "Net-(U7C-A)") (class "Default")
      (node (ref "R71") (pin "1") (pinfunction "1_1") (pintype "passive"))
      (node (ref "U7") (pin "5") (pinfunction "A_5") (pintype "passive"))
    )
    (net (code "54") (name "Net-(U7D-A)") (class "Default")
      (node (ref "R72") (pin "1") (pinfunction "1_1") (pintype "passive"))
      (node (ref "U7") (pin "7") (pinfunction "A_7") (pintype "passive"))
    )
    (net (code "55") (name "Net-(U8A-A)") (class "Default")
      (node (ref "R73") (pin "1") (pinfunction "1_1") (pintype "passive"))
      (node (ref "U8") (pin "1") (pinfunction "A_1") (pintype "passive"))
    )
    (net (code "56") (name "Net-(U8B-A)") (class "Default")
      (node (ref "R74") (pin "1") (pinfunction "1_1") (pintype "passive"))
      (node (ref "U8") (pin "3") (pinfunction "A_3") (pintype "passive"))
    )
    (net (code "57") (name "Net-(U8C-A)") (class "Default")
      (node (ref "R75") (pin "1") (pinfunction "1_1") (pintype "passive"))
      (node (ref "U8") (pin "5") (pinfunction "A_5") (pintype "passive"))
    )
    (net (code "58") (name "Net-(U8D-A)") (class "Default")
      (node (ref "R76") (pin "1") (pinfunction "1_1") (pintype "passive"))
      (node (ref "U8") (pin "7") (pinfunction "A_7") (pintype "passive"))
    )
    (net (code "59") (name "Net-(U9A-A)") (class "Default")
      (node (ref "R51") (pin "1") (pinfunction "1_1") (pintype "passive"))
      (node (ref "U9") (pin "1") (pinfunction "A_1") (pintype "passive"))
    )
    (net (code "60") (name "Net-(U9A-OUT)") (class "Default")
      (node (ref "R54") (pin "2") (pinfunction "2_2") (pintype "passive"))
      (node (ref "U9") (pin "7") (pinfunction "OUT_7") (pintype "passive"))
    )
    (net (code "61") (name "Net-(U9B-A)") (class "Default")
      (node (ref "R52") (pin "1") (pinfunction "1_1") (pintype "passive"))
      (node (ref "U9") (pin "4") (pinfunction "A_4") (pintype "passive"))
    )
    (net (code "62") (name "Net-(U9B-OUT)") (class "Default")
      (node (ref "R53") (pin "2") (pinfunction "2_2") (pintype "passive"))
      (node (ref "U9") (pin "6") (pinfunction "OUT_6") (pintype "passive"))
    )
    (net (code "63") (name "Net-(X1B-S)") (class "Default")
      (node (ref "R15") (pin "1") (pinfunction "1_1") (pintype "passive"))
      (node (ref "R16") (pin "1") (pinfunction "1_1") (pintype "passive"))
      (node (ref "X1") (pin "10") (pinfunction "S_10") (pintype "passive"))
    )
    (net (code "64") (name "Net-(X1G-S)") (class "Default")
      (node (ref "R17") (pin "1") (pinfunction "1_1") (pintype "passive"))
      (node (ref "R18") (pin "1") (pinfunction "1_1") (pintype "passive"))
      (node (ref "X1") (pin "15") (pinfunction "S_15") (pintype "passive"))
    )
    (net (code "65") (name "Net-(X1H-S)") (class "Default")
      (node (ref "R19") (pin "1") (pinfunction "1_1") (pintype "passive"))
      (node (ref "R20") (pin "1") (pinfunction "1_1") (pintype "passive"))
      (node (ref "X1") (pin "16") (pinfunction "S_16") (pintype "passive"))
    )
    (net (code "66") (name "Net-(X1I-S)") (class "Default")
      (node (ref "R21") (pin "1") (pinfunction "1_1") (pintype "passive"))
      (node (ref "R22") (pin "1") (pinfunction "1_1") (pintype "passive"))
      (node (ref "X1") (pin "17") (pinfunction "S_17") (pintype "passive"))
    )
    (net (code "67") (name "Net-(X1J-S)") (class "Default")
      (node (ref "R23") (pin "1") (pinfunction "1_1") (pintype "passive"))
      (node (ref "R24") (pin "1") (pinfunction "1_1") (pintype "passive"))
      (node (ref "X1") (pin "18") (pinfunction "S_18") (pintype "passive"))
    )
    (net (code "68") (name "Net-(X1K-S)") (class "Default")
      (node (ref "R25") (pin "1") (pinfunction "1_1") (pintype "passive"))
      (node (ref "R26") (pin "1") (pinfunction "1_1") (pintype "passive"))
      (node (ref "X1") (pin "19") (pinfunction "S_19") (pintype "passive"))
    )
    (net (code "69") (name "Net-(X1M-S)") (class "Default")
      (node (ref "R27") (pin "1") (pinfunction "1_1") (pintype "passive"))
      (node (ref "R28") (pin "1") (pinfunction "1_1") (pintype "passive"))
      (node (ref "X1") (pin "20") (pinfunction "S_20") (pintype "passive"))
    )
    (net (code "70") (name "Net-(X1N-S)") (class "Default")
      (node (ref "R29") (pin "1") (pinfunction "1_1") (pintype "passive"))
      (node (ref "R30") (pin "1") (pinfunction "1_1") (pintype "passive"))
      (node (ref "X1") (pin "21") (pinfunction "S_21") (pintype "passive"))
    )
    (net (code "71") (name "Net-(X1O-S)") (class "Default")
      (node (ref "R31") (pin "1") (pinfunction "1_1") (pintype "passive"))
      (node (ref "R32") (pin "1") (pinfunction "1_1") (pintype "passive"))
      (node (ref "X1") (pin "22") (pinfunction "S_22") (pintype "passive"))
    )
    (net (code "72") (name "Net-(X1T-S)") (class "Default")
      (node (ref "R1") (pin "1") (pinfunction "1_1") (pintype "passive"))
      (node (ref "R2") (pin "1") (pinfunction "1_1") (pintype "passive"))
      (node (ref "X1") (pin "3") (pinfunction "S_3") (pintype "passive"))
    )
    (net (code "73") (name "Net-(X1U-S)") (class "Default")
      (node (ref "R3") (pin "1") (pinfunction "1_1") (pintype "passive"))
      (node (ref "R4") (pin "1") (pinfunction "1_1") (pintype "passive"))
      (node (ref "X1") (pin "4") (pinfunction "S_4") (pintype "passive"))
    )
    (net (code "74") (name "Net-(X1V-S)") (class "Default")
      (node (ref "R5") (pin "1") (pinfunction "1_1") (pintype "passive"))
      (node (ref "R6") (pin "1") (pinfunction "1_1") (pintype "passive"))
      (node (ref "X1") (pin "5") (pinfunction "S_5") (pintype "passive"))
    )
    (net (code "75") (name "Net-(X1W-S)") (class "Default")
      (node (ref "R7") (pin "1") (pinfunction "1_1") (pintype "passive"))
      (node (ref "R8") (pin "1") (pinfunction "1_1") (pintype "passive"))
      (node (ref "X1") (pin "6") (pinfunction "S_6") (pintype "passive"))
    )
    (net (code "76") (name "Net-(X1X-S)") (class "Default")
      (node (ref "R10") (pin "1") (pinfunction "1_1") (pintype "passive"))
      (node (ref "R9") (pin "1") (pinfunction "1_1") (pintype "passive"))
      (node (ref "X1") (pin "7") (pinfunction "S_7") (pintype "passive"))
    )
    (net (code "77") (name "Net-(X1Y-S)") (class "Default")
      (node (ref "R11") (pin "1") (pinfunction "1_1") (pintype "passive"))
      (node (ref "R12") (pin "1") (pinfunction "1_1") (pintype "passive"))
      (node (ref "X1") (pin "8") (pinfunction "S_8") (pintype "passive"))
    )
    (net (code "78") (name "Net-(X1Z-S)") (class "Default")
      (node (ref "R13") (pin "1") (pinfunction "1_1") (pintype "passive"))
      (node (ref "R14") (pin "1") (pinfunction "1_1") (pintype "passive"))
      (node (ref "X1") (pin "9") (pinfunction "S_9") (pintype "passive"))
    )
    (net (code "79") (name "PORT1-3") (class "Default")
      (node (ref "PORT1") (pin "3") (pinfunction "S_3") (pintype "passive"))
      (node (ref "R55") (pin "2") (pinfunction "2_2") (pintype "passive"))
      (node (ref "R56") (pin "2") (pinfunction "2_2") (pintype "passive"))
      (node (ref "R57") (pin "2") (pinfunction "2_2") (pintype "passive"))
    )
    (net (code "80") (name "PORT1-5") (class "Default")
      (node (ref "PORT1") (pin "5") (pinfunction "S_5") (pintype "passive"))
      (node (ref "R58") (pin "2") (pinfunction "2_2") (pintype "passive"))
      (node (ref "R59") (pin "2") (pinfunction "2_2") (pintype "passive"))
      (node (ref "R60") (pin "2") (pinfunction "2_2") (pintype "passive"))
    )
    (net (code "81") (name "PORT1_VSS") (class "Default")
      (node (ref "C1") (pin "2") (pinfunction "2_2") (pintype "passive"))
      (node (ref "JP1") (pin "11") (pinfunction "11_11") (pintype "passive"))
      (node (ref "JP1") (pin "5") (pinfunction "5_5") (pintype "passive"))
      (node (ref "JP1") (pin "7") (pinfunction "7_7") (pintype "passive"))
      (node (ref "JP1") (pin "9") (pinfunction "9_9") (pintype "passive"))
      (node (ref "PORT1") (pin "2") (pinfunction "S_2") (pintype "passive"))
      (node (ref "R34") (pin "1") (pinfunction "1_1") (pintype "passive"))
      (node (ref "R35") (pin "1") (pinfunction "1_1") (pintype "passive"))
      (node (ref "R36") (pin "1") (pinfunction "1_1") (pintype "passive"))
      (node (ref "R37") (pin "1") (pinfunction "1_1") (pintype "passive"))
      (node (ref "R38") (pin "1") (pinfunction "1_1") (pintype "passive"))
      (node (ref "R39") (pin "1") (pinfunction "1_1") (pintype "passive"))
      (node (ref "R40") (pin "1") (pinfunction "1_1") (pintype "passive"))
      (node (ref "R41") (pin "1") (pinfunction "1_1") (pintype "passive"))
      (node (ref "U5") (pin "2") (pinfunction "C_2") (pintype "passive"))
      (node (ref "U5") (pin "4") (pinfunction "C_4") (pintype "passive"))
      (node (ref "U5") (pin "6") (pinfunction "C_6") (pintype "passive"))
      (node (ref "U5") (pin "8") (pinfunction "C_8") (pintype "passive"))
      (node (ref "U6") (pin "2") (pinfunction "C_2") (pintype "passive"))
      (node (ref "U6") (pin "4") (pinfunction "C_4") (pintype "passive"))
      (node (ref "U6") (pin "6") (pinfunction "C_6") (pintype "passive"))
      (node (ref "U6") (pin "8") (pinfunction "C_8") (pintype "passive"))
      (node (ref "U9") (pin "2") (pinfunction "C_2") (pintype "passive"))
      (node (ref "U9") (pin "3") (pinfunction "C_3") (pintype "passive"))
    )
    (net (code "82") (name "PORT2_VSS") (class "Default")
      (node (ref "C2") (pin "2") (pinfunction "2_2") (pintype "passive"))
      (node (ref "JP6") (pin "10") (pinfunction "10_10") (pintype "passive"))
      (node (ref "JP6") (pin "12") (pinfunction "12_12") (pintype "passive"))
      (node (ref "JP6") (pin "6") (pinfunction "6_6") (pintype "passive"))
      (node (ref "JP6") (pin "8") (pinfunction "8_8") (pintype "passive"))
      (node (ref "PORT2") (pin "2") (pinfunction "S_2") (pintype "passive"))
      (node (ref "R42") (pin "1") (pinfunction "1_1") (pintype "passive"))
      (node (ref "R43") (pin "1") (pinfunction "1_1") (pintype "passive"))
      (node (ref "R44") (pin "1") (pinfunction "1_1") (pintype "passive"))
      (node (ref "R45") (pin "1") (pinfunction "1_1") (pintype "passive"))
      (node (ref "R46") (pin "1") (pinfunction "1_1") (pintype "passive"))
      (node (ref "R47") (pin "1") (pinfunction "1_1") (pintype "passive"))
      (node (ref "R48") (pin "1") (pinfunction "1_1") (pintype "passive"))
      (node (ref "R49") (pin "1") (pinfunction "1_1") (pintype "passive"))
      (node (ref "U7") (pin "2") (pinfunction "C_2") (pintype "passive"))
      (node (ref "U7") (pin "4") (pinfunction "C_4") (pintype "passive"))
      (node (ref "U7") (pin "6") (pinfunction "C_6") (pintype "passive"))
      (node (ref "U7") (pin "8") (pinfunction "C_8") (pintype "passive"))
      (node (ref "U8") (pin "2") (pinfunction "C_2") (pintype "passive"))
      (node (ref "U8") (pin "4") (pinfunction "C_4") (pintype "passive"))
      (node (ref "U8") (pin "6") (pinfunction "C_6") (pintype "passive"))
      (node (ref "U8") (pin "8") (pinfunction "C_8") (pintype "passive"))
    )
    (net (code "83") (name "PWM") (class "Default")
      (node (ref "R53") (pin "1") (pinfunction "1_1") (pintype "passive"))
      (node (ref "X1") (pin "13") (pinfunction "S_13") (pintype "passive"))
    )
    (net (code "84") (name "R1") (class "Default")
      (node (ref "R1") (pin "2") (pinfunction "2_2") (pintype "passive"))
      (node (ref "U1") (pin "1") (pinfunction "A_1") (pintype "passive"))
      (node (ref "U5") (pin "15") (pinfunction "EMIT_15") (pintype "passive"))
    )
    (net (code "85") (name "R3") (class "Default")
      (node (ref "R3") (pin "2") (pinfunction "2_2") (pintype "passive"))
      (node (ref "U1") (pin "3") (pinfunction "A_3") (pintype "passive"))
      (node (ref "U5") (pin "13") (pinfunction "EMIT_13") (pintype "passive"))
    )
    (net (code "86") (name "R5") (class "Default")
      (node (ref "R5") (pin "2") (pinfunction "2_2") (pintype "passive"))
      (node (ref "U1") (pin "5") (pinfunction "A_5") (pintype "passive"))
      (node (ref "U5") (pin "11") (pinfunction "EMIT_11") (pintype "passive"))
    )
    (net (code "87") (name "R7") (class "Default")
      (node (ref "R7") (pin "2") (pinfunction "2_2") (pintype "passive"))
      (node (ref "U1") (pin "7") (pinfunction "A_7") (pintype "passive"))
      (node (ref "U5") (pin "9") (pinfunction "EMIT_9") (pintype "passive"))
    )
    (net (code "88") (name "R9") (class "Default")
      (node (ref "R9") (pin "2") (pinfunction "2_2") (pintype "passive"))
      (node (ref "U2") (pin "1") (pinfunction "A_1") (pintype "passive"))
      (node (ref "U6") (pin "15") (pinfunction "EMIT_15") (pintype "passive"))
    )
    (net (code "89") (name "R11") (class "Default")
      (node (ref "R11") (pin "2") (pinfunction "2_2") (pintype "passive"))
      (node (ref "U2") (pin "3") (pinfunction "A_3") (pintype "passive"))
      (node (ref "U6") (pin "13") (pinfunction "EMIT_13") (pintype "passive"))
    )
    (net (code "90") (name "R13") (class "Default")
      (node (ref "R13") (pin "2") (pinfunction "2_2") (pintype "passive"))
      (node (ref "U2") (pin "5") (pinfunction "A_5") (pintype "passive"))
      (node (ref "U6") (pin "11") (pinfunction "EMIT_11") (pintype "passive"))
    )
    (net (code "91") (name "R15") (class "Default")
      (node (ref "R15") (pin "2") (pinfunction "2_2") (pintype "passive"))
      (node (ref "U2") (pin "7") (pinfunction "A_7") (pintype "passive"))
      (node (ref "U6") (pin "9") (pinfunction "EMIT_9") (pintype "passive"))
    )
    (net (code "92") (name "R17") (class "Default")
      (node (ref "R17") (pin "2") (pinfunction "2_2") (pintype "passive"))
      (node (ref "U3") (pin "1") (pinfunction "A_1") (pintype "passive"))
      (node (ref "U7") (pin "15") (pinfunction "EMIT_15") (pintype "passive"))
    )
    (net (code "93") (name "R19") (class "Default")
      (node (ref "R19") (pin "2") (pinfunction "2_2") (pintype "passive"))
      (node (ref "U3") (pin "3") (pinfunction "A_3") (pintype "passive"))
      (node (ref "U7") (pin "13") (pinfunction "EMIT_13") (pintype "passive"))
    )
    (net (code "94") (name "R21") (class "Default")
      (node (ref "R21") (pin "2") (pinfunction "2_2") (pintype "passive"))
      (node (ref "U3") (pin "5") (pinfunction "A_5") (pintype "passive"))
      (node (ref "U7") (pin "11") (pinfunction "EMIT_11") (pintype "passive"))
    )
    (net (code "95") (name "R23") (class "Default")
      (node (ref "R23") (pin "2") (pinfunction "2_2") (pintype "passive"))
      (node (ref "U3") (pin "7") (pinfunction "A_7") (pintype "passive"))
      (node (ref "U7") (pin "9") (pinfunction "EMIT_9") (pintype "passive"))
    )
    (net (code "96") (name "R25") (class "Default")
      (node (ref "R25") (pin "2") (pinfunction "2_2") (pintype "passive"))
      (node (ref "U4") (pin "1") (pinfunction "A_1") (pintype "passive"))
      (node (ref "U8") (pin "15") (pinfunction "EMIT_15") (pintype "passive"))
    )
    (net (code "97") (name "R27") (class "Default")
      (node (ref "R27") (pin "2") (pinfunction "2_2") (pintype "passive"))
      (node (ref "U4") (pin "3") (pinfunction "A_3") (pintype "passive"))
      (node (ref "U8") (pin "13") (pinfunction "EMIT_13") (pintype "passive"))
    )
    (net (code "98") (name "R29") (class "Default")
      (node (ref "R29") (pin "2") (pinfunction "2_2") (pintype "passive"))
      (node (ref "U4") (pin "5") (pinfunction "A_5") (pintype "passive"))
      (node (ref "U8") (pin "11") (pinfunction "EMIT_11") (pintype "passive"))
    )
    (net (code "99") (name "R31") (class "Default")
      (node (ref "R31") (pin "2") (pinfunction "2_2") (pintype "passive"))
      (node (ref "U4") (pin "7") (pinfunction "A_7") (pintype "passive"))
      (node (ref "U8") (pin "9") (pinfunction "EMIT_9") (pintype "passive"))
    )
    (net (code "100") (name "unconnected-(JP1-Pad4)") (class "Default")
      (node (ref "JP1") (pin "4") (pinfunction "4_4") (pintype "passive"))
    )
    (net (code "101") (name "unconnected-(JP1-Pad6)") (class "Default")
      (node (ref "JP1") (pin "6") (pinfunction "6_6") (pintype "passive"))
    )
    (net (code "102") (name "unconnected-(JP1-Pad8)") (class "Default")
      (node (ref "JP1") (pin "8") (pinfunction "8_8") (pintype "passive"))
    )
    (net (code "103") (name "unconnected-(JP1-Pad10)") (class "Default")
      (node (ref "JP1") (pin "10") (pinfunction "10_10") (pintype "passive"))
    )
    (net (code "104") (name "unconnected-(JP1-Pad12)") (class "Default")
      (node (ref "JP1") (pin "12") (pinfunction "12_12") (pintype "passive"))
    )
    (net (code "105") (name "unconnected-(JP1-Pad13)") (class "Default")
      (node (ref "JP1") (pin "13") (pinfunction "13_13") (pintype "passive"))
    )
    (net (code "106") (name "unconnected-(JP1-Pad14)") (class "Default")
      (node (ref "JP1") (pin "14") (pinfunction "14_14") (pintype "passive"))
    )
    (net (code "107") (name "unconnected-(JP1-Pad15)") (class "Default")
      (node (ref "JP1") (pin "15") (pinfunction "15_15") (pintype "passive"))
    )
    (net (code "108") (name "unconnected-(JP1-Pad16)") (class "Default")
      (node (ref "JP1") (pin "16") (pinfunction "16_16") (pintype "passive"))
    )
    (net (code "109") (name "unconnected-(JP1-Pad17)") (class "Default")
      (node (ref "JP1") (pin "17") (pinfunction "17_17") (pintype "passive"))
    )
    (net (code "110") (name "unconnected-(JP1-Pad18)") (class "Default")
      (node (ref "JP1") (pin "18") (pinfunction "18_18") (pintype "passive"))
    )
    (net (code "111") (name "unconnected-(JP1-Pad19)") (class "Default")
      (node (ref "JP1") (pin "19") (pinfunction "19_19") (pintype "passive"))
    )
    (net (code "112") (name "unconnected-(JP1-Pad20)") (class "Default")
      (node (ref "JP1") (pin "20") (pinfunction "20_20") (pintype "passive"))
    )
    (net (code "113") (name "unconnected-(JP1-Pad21)") (class "Default")
      (node (ref "JP1") (pin "21") (pinfunction "21_21") (pintype "passive"))
    )
    (net (code "114") (name "unconnected-(JP1-Pad22)") (class "Default")
      (node (ref "JP1") (pin "22") (pinfunction "22_22") (pintype "passive"))
    )
    (net (code "115") (name "unconnected-(JP1-Pad23)") (class "Default")
      (node (ref "JP1") (pin "23") (pinfunction "23_23") (pintype "passive"))
    )
    (net (code "116") (name "unconnected-(JP1-Pad24)") (class "Default")
      (node (ref "JP1") (pin "24") (pinfunction "24_24") (pintype "passive"))
    )
    (net (code "117") (name "unconnected-(JP2-Pad3)") (class "Default")
      (node (ref "JP2") (pin "3") (pinfunction "3_3") (pintype "passive"))
    )
    (net (code "118") (name "unconnected-(JP2-Pad4)") (class "Default")
      (node (ref "JP2") (pin "4") (pinfunction "4_4") (pintype "passive"))
    )
    (net (code "119") (name "unconnected-(JP2-Pad5)") (class "Default")
      (node (ref "JP2") (pin "5") (pinfunction "5_5") (pintype "passive"))
    )
    (net (code "120") (name "unconnected-(JP2-Pad6)") (class "Default")
      (node (ref "JP2") (pin "6") (pinfunction "6_6") (pintype "passive"))
    )
    (net (code "121") (name "unconnected-(JP2-Pad7)") (class "Default")
      (node (ref "JP2") (pin "7") (pinfunction "7_7") (pintype "passive"))
    )
    (net (code "122") (name "unconnected-(JP2-Pad8)") (class "Default")
      (node (ref "JP2") (pin "8") (pinfunction "8_8") (pintype "passive"))
    )
    (net (code "123") (name "unconnected-(JP2-Pad9)") (class "Default")
      (node (ref "JP2") (pin "9") (pinfunction "9_9") (pintype "passive"))
    )
    (net (code "124") (name "unconnected-(JP2-Pad10)") (class "Default")
      (node (ref "JP2") (pin "10") (pinfunction "10_10") (pintype "passive"))
    )
    (net (code "125") (name "unconnected-(JP2-Pad11)") (class "Default")
      (node (ref "JP2") (pin "11") (pinfunction "11_11") (pintype "passive"))
    )
    (net (code "126") (name "unconnected-(JP2-Pad12)") (class "Default")
      (node (ref "JP2") (pin "12") (pinfunction "12_12") (pintype "passive"))
    )
    (net (code "127") (name "unconnected-(JP2-Pad13)") (class "Default")
      (node (ref "JP2") (pin "13") (pinfunction "13_13") (pintype "passive"))
    )
    (net (code "128") (name "unconnected-(JP2-Pad14)") (class "Default")
      (node (ref "JP2") (pin "14") (pinfunction "14_14") (pintype "passive"))
    )
    (net (code "129") (name "unconnected-(JP2-Pad15)") (class "Default")
      (node (ref "JP2") (pin "15") (pinfunction "15_15") (pintype "passive"))
    )
    (net (code "130") (name "unconnected-(JP2-Pad16)") (class "Default")
      (node (ref "JP2") (pin "16") (pinfunction "16_16") (pintype "passive"))
    )
    (net (code "131") (name "unconnected-(JP2-Pad17)") (class "Default")
      (node (ref "JP2") (pin "17") (pinfunction "17_17") (pintype "passive"))
    )
    (net (code "132") (name "unconnected-(JP2-Pad18)") (class "Default")
      (node (ref "JP2") (pin "18") (pinfunction "18_18") (pintype "passive"))
    )
    (net (code "133") (name "unconnected-(JP2-Pad19)") (class "Default")
      (node (ref "JP2") (pin "19") (pinfunction "19_19") (pintype "passive"))
    )
    (net (code "134") (name "unconnected-(JP2-Pad20)") (class "Default")
      (node (ref "JP2") (pin "20") (pinfunction "20_20") (pintype "passive"))
    )
    (net (code "135") (name "unconnected-(JP2-Pad21)") (class "Default")
      (node (ref "JP2") (pin "21") (pinfunction "21_21") (pintype "passive"))
    )
    (net (code "136") (name "unconnected-(JP2-Pad22)") (class "Default")
      (node (ref "JP2") (pin "22") (pinfunction "22_22") (pintype "passive"))
    )
    (net (code "137") (name "unconnected-(JP2-Pad23)") (class "Default")
      (node (ref "JP2") (pin "23") (pinfunction "23_23") (pintype "passive"))
    )
    (net (code "138") (name "unconnected-(JP2-Pad24)") (class "Default")
      (node (ref "JP2") (pin "24") (pinfunction "24_24") (pintype "passive"))
    )
    (net (code "139") (name "unconnected-(JP3-Pad1)") (class "Default")
      (node (ref "JP3") (pin "1") (pinfunction "1_1") (pintype "passive"))
    )
    (net (code "140") (name "unconnected-(JP3-Pad2)") (class "Default")
      (node (ref "JP3") (pin "2") (pinfunction "2_2") (pintype "passive"))
    )
    (net (code "141") (name "unconnected-(JP3-Pad3)") (class "Default")
      (node (ref "JP3") (pin "3") (pinfunction "3_3") (pintype "passive"))
    )
    (net (code "142") (name "unconnected-(JP3-Pad4)") (class "Default")
      (node (ref "JP3") (pin "4") (pinfunction "4_4") (pintype "passive"))
    )
    (net (code "143") (name "unconnected-(JP3-Pad5)") (class "Default")
      (node (ref "JP3") (pin "5") (pinfunction "5_5") (pintype "passive"))
    )
    (net (code "144") (name "unconnected-(JP3-Pad6)") (class "Default")
      (node (ref "JP3") (pin "6") (pinfunction "6_6") (pintype "passive"))
    )
    (net (code "145") (name "unconnected-(JP3-Pad7)") (class "Default")
      (node (ref "JP3") (pin "7") (pinfunction "7_7") (pintype "passive"))
    )
    (net (code "146") (name "unconnected-(JP3-Pad8)") (class "Default")
      (node (ref "JP3") (pin "8") (pinfunction "8_8") (pintype "passive"))
    )
    (net (code "147") (name "unconnected-(JP3-Pad9)") (class "Default")
      (node (ref "JP3") (pin "9") (pinfunction "9_9") (pintype "passive"))
    )
    (net (code "148") (name "unconnected-(JP3-Pad10)") (class "Default")
      (node (ref "JP3") (pin "10") (pinfunction "10_10") (pintype "passive"))
    )
    (net (code "149") (name "unconnected-(JP3-Pad11)") (class "Default")
      (node (ref "JP3") (pin "11") (pinfunction "11_11") (pintype "passive"))
    )
    (net (code "150") (name "unconnected-(JP3-Pad12)") (class "Default")
      (node (ref "JP3") (pin "12") (pinfunction "12_12") (pintype "passive"))
    )
    (net (code "151") (name "unconnected-(JP3-Pad13)") (class "Default")
      (node (ref "JP3") (pin "13") (pinfunction "13_13") (pintype "passive"))
    )
    (net (code "152") (name "unconnected-(JP3-Pad14)") (class "Default")
      (node (ref "JP3") (pin "14") (pinfunction "14_14") (pintype "passive"))
    )
    (net (code "153") (name "unconnected-(JP3-Pad15)") (class "Default")
      (node (ref "JP3") (pin "15") (pinfunction "15_15") (pintype "passive"))
    )
    (net (code "154") (name "unconnected-(JP3-Pad16)") (class "Default")
      (node (ref "JP3") (pin "16") (pinfunction "16_16") (pintype "passive"))
    )
    (net (code "155") (name "unconnected-(JP3-Pad17)") (class "Default")
      (node (ref "JP3") (pin "17") (pinfunction "17_17") (pintype "passive"))
    )
    (net (code "156") (name "unconnected-(JP3-Pad18)") (class "Default")
      (node (ref "JP3") (pin "18") (pinfunction "18_18") (pintype "passive"))
    )
    (net (code "157") (name "unconnected-(JP3-Pad19)") (class "Default")
      (node (ref "JP3") (pin "19") (pinfunction "19_19") (pintype "passive"))
    )
    (net (code "158") (name "unconnected-(JP3-Pad20)") (class "Default")
      (node (ref "JP3") (pin "20") (pinfunction "20_20") (pintype "passive"))
    )
    (net (code "159") (name "unconnected-(JP3-Pad21)") (class "Default")
      (node (ref "JP3") (pin "21") (pinfunction "21_21") (pintype "passive"))
    )
    (net (code "160") (name "unconnected-(JP3-Pad22)") (class "Default")
      (node (ref "JP3") (pin "22") (pinfunction "22_22") (pintype "passive"))
    )
    (net (code "161") (name "unconnected-(JP3-Pad23)") (class "Default")
      (node (ref "JP3") (pin "23") (pinfunction "23_23") (pintype "passive"))
    )
    (net (code "162") (name "unconnected-(JP3-Pad24)") (class "Default")
      (node (ref "JP3") (pin "24") (pinfunction "24_24") (pintype "passive"))
    )
    (net (code "163") (name "unconnected-(JP4-Pad1)") (class "Default")
      (node (ref "JP4") (pin "1") (pinfunction "1_1") (pintype "passive"))
    )
    (net (code "164") (name "unconnected-(JP4-Pad2)") (class "Default")
      (node (ref "JP4") (pin "2") (pinfunction "2_2") (pintype "passive"))
    )
    (net (code "165") (name "unconnected-(JP4-Pad3)") (class "Default")
      (node (ref "JP4") (pin "3") (pinfunction "3_3") (pintype "passive"))
    )
    (net (code "166") (name "unconnected-(JP4-Pad4)") (class "Default")
      (node (ref "JP4") (pin "4") (pinfunction "4_4") (pintype "passive"))
    )
    (net (code "167") (name "unconnected-(JP4-Pad5)") (class "Default")
      (node (ref "JP4") (pin "5") (pinfunction "5_5") (pintype "passive"))
    )
    (net (code "168") (name "unconnected-(JP4-Pad6)") (class "Default")
      (node (ref "JP4") (pin "6") (pinfunction "6_6") (pintype "passive"))
    )
    (net (code "169") (name "unconnected-(JP4-Pad7)") (class "Default")
      (node (ref "JP4") (pin "7") (pinfunction "7_7") (pintype "passive"))
    )
    (net (code "170") (name "unconnected-(JP4-Pad8)") (class "Default")
      (node (ref "JP4") (pin "8") (pinfunction "8_8") (pintype "passive"))
    )
    (net (code "171") (name "unconnected-(JP4-Pad9)") (class "Default")
      (node (ref "JP4") (pin "9") (pinfunction "9_9") (pintype "passive"))
    )
    (net (code "172") (name "unconnected-(JP4-Pad10)") (class "Default")
      (node (ref "JP4") (pin "10") (pinfunction "10_10") (pintype "passive"))
    )
    (net (code "173") (name "unconnected-(JP4-Pad11)") (class "Default")
      (node (ref "JP4") (pin "11") (pinfunction "11_11") (pintype "passive"))
    )
    (net (code "174") (name "unconnected-(JP4-Pad12)") (class "Default")
      (node (ref "JP4") (pin "12") (pinfunction "12_12") (pintype "passive"))
    )
    (net (code "175") (name "unconnected-(JP4-Pad13)") (class "Default")
      (node (ref "JP4") (pin "13") (pinfunction "13_13") (pintype "passive"))
    )
    (net (code "176") (name "unconnected-(JP4-Pad14)") (class "Default")
      (node (ref "JP4") (pin "14") (pinfunction "14_14") (pintype "passive"))
    )
    (net (code "177") (name "unconnected-(JP4-Pad15)") (class "Default")
      (node (ref "JP4") (pin "15") (pinfunction "15_15") (pintype "passive"))
    )
    (net (code "178") (name "unconnected-(JP4-Pad16)") (class "Default")
      (node (ref "JP4") (pin "16") (pinfunction "16_16") (pintype "passive"))
    )
    (net (code "179") (name "unconnected-(JP4-Pad17)") (class "Default")
      (node (ref "JP4") (pin "17") (pinfunction "17_17") (pintype "passive"))
    )
    (net (code "180") (name "unconnected-(JP4-Pad18)") (class "Default")
      (node (ref "JP4") (pin "18") (pinfunction "18_18") (pintype "passive"))
    )
    (net (code "181") (name "unconnected-(JP4-Pad19)") (class "Default")
      (node (ref "JP4") (pin "19") (pinfunction "19_19") (pintype "passive"))
    )
    (net (code "182") (name "unconnected-(JP4-Pad20)") (class "Default")
      (node (ref "JP4") (pin "20") (pinfunction "20_20") (pintype "passive"))
    )
    (net (code "183") (name "unconnected-(JP4-Pad21)") (class "Default")
      (node (ref "JP4") (pin "21") (pinfunction "21_21") (pintype "passive"))
    )
    (net (code "184") (name "unconnected-(JP4-Pad22)") (class "Default")
      (node (ref "JP4") (pin "22") (pinfunction "22_22") (pintype "passive"))
    )
    (net (code "185") (name "unconnected-(JP4-Pad23)") (class "Default")
      (node (ref "JP4") (pin "23") (pinfunction "23_23") (pintype "passive"))
    )
    (net (code "186") (name "unconnected-(JP4-Pad24)") (class "Default")
      (node (ref "JP4") (pin "24") (pinfunction "24_24") (pintype "passive"))
    )
    (net (code "187") (name "unconnected-(JP5-Pad3)") (class "Default")
      (node (ref "JP5") (pin "3") (pinfunction "3_3") (pintype "passive"))
    )
    (net (code "188") (name "unconnected-(JP5-Pad4)") (class "Default")
      (node (ref "JP5") (pin "4") (pinfunction "4_4") (pintype "passive"))
    )
    (net (code "189") (name "unconnected-(JP5-Pad5)") (class "Default")
      (node (ref "JP5") (pin "5") (pinfunction "5_5") (pintype "passive"))
    )
    (net (code "190") (name "unconnected-(JP5-Pad6)") (class "Default")
      (node (ref "JP5") (pin "6") (pinfunction "6_6") (pintype "passive"))
    )
    (net (code "191") (name "unconnected-(JP5-Pad7)") (class "Default")
      (node (ref "JP5") (pin "7") (pinfunction "7_7") (pintype "passive"))
    )
    (net (code "192") (name "unconnected-(JP5-Pad8)") (class "Default")
      (node (ref "JP5") (pin "8") (pinfunction "8_8") (pintype "passive"))
    )
    (net (code "193") (name "unconnected-(JP5-Pad9)") (class "Default")
      (node (ref "JP5") (pin "9") (pinfunction "9_9") (pintype "passive"))
    )
    (net (code "194") (name "unconnected-(JP5-Pad10)") (class "Default")
      (node (ref "JP5") (pin "10") (pinfunction "10_10") (pintype "passive"))
    )
    (net (code "195") (name "unconnected-(JP5-Pad11)") (class "Default")
      (node (ref "JP5") (pin "11") (pinfunction "11_11") (pintype "passive"))
    )
    (net (code "196") (name "unconnected-(JP5-Pad12)") (class "Default")
      (node (ref "JP5") (pin "12") (pinfunction "12_12") (pintype "passive"))
    )
    (net (code "197") (name "unconnected-(JP5-Pad13)") (class "Default")
      (node (ref "JP5") (pin "13") (pinfunction "13_13") (pintype "passive"))
    )
    (net (code "198") (name "unconnected-(JP5-Pad14)") (class "Default")
      (node (ref "JP5") (pin "14") (pinfunction "14_14") (pintype "passive"))
    )
    (net (code "199") (name "unconnected-(JP5-Pad15)") (class "Default")
      (node (ref "JP5") (pin "15") (pinfunction "15_15") (pintype "passive"))
    )
    (net (code "200") (name "unconnected-(JP5-Pad16)") (class "Default")
      (node (ref "JP5") (pin "16") (pinfunction "16_16") (pintype "passive"))
    )
    (net (code "201") (name "unconnected-(JP5-Pad17)") (class "Default")
      (node (ref "JP5") (pin "17") (pinfunction "17_17") (pintype "passive"))
    )
    (net (code "202") (name "unconnected-(JP5-Pad18)") (class "Default")
      (node (ref "JP5") (pin "18") (pinfunction "18_18") (pintype "passive"))
    )
    (net (code "203") (name "unconnected-(JP5-Pad19)") (class "Default")
      (node (ref "JP5") (pin "19") (pinfunction "19_19") (pintype "passive"))
    )
    (net (code "204") (name "unconnected-(JP5-Pad20)") (class "Default")
      (node (ref "JP5") (pin "20") (pinfunction "20_20") (pintype "passive"))
    )
    (net (code "205") (name "unconnected-(JP5-Pad21)") (class "Default")
      (node (ref "JP5") (pin "21") (pinfunction "21_21") (pintype "passive"))
    )
    (net (code "206") (name "unconnected-(JP5-Pad22)") (class "Default")
      (node (ref "JP5") (pin "22") (pinfunction "22_22") (pintype "passive"))
    )
    (net (code "207") (name "unconnected-(JP5-Pad23)") (class "Default")
      (node (ref "JP5") (pin "23") (pinfunction "23_23") (pintype "passive"))
    )
    (net (code "208") (name "unconnected-(JP5-Pad24)") (class "Default")
      (node (ref "JP5") (pin "24") (pinfunction "24_24") (pintype "passive"))
    )
    (net (code "209") (name "unconnected-(JP6-Pad3)") (class "Default")
      (node (ref "JP6") (pin "3") (pinfunction "3_3") (pintype "passive"))
    )
    (net (code "210") (name "unconnected-(JP6-Pad5)") (class "Default")
      (node (ref "JP6") (pin "5") (pinfunction "5_5") (pintype "passive"))
    )
    (net (code "211") (name "unconnected-(JP6-Pad7)") (class "Default")
      (node (ref "JP6") (pin "7") (pinfunction "7_7") (pintype "passive"))
    )
    (net (code "212") (name "unconnected-(JP6-Pad9)") (class "Default")
      (node (ref "JP6") (pin "9") (pinfunction "9_9") (pintype "passive"))
    )
    (net (code "213") (name "unconnected-(JP6-Pad11)") (class "Default")
      (node (ref "JP6") (pin "11") (pinfunction "11_11") (pintype "passive"))
    )
    (net (code "214") (name "unconnected-(JP6-Pad13)") (class "Default")
      (node (ref "JP6") (pin "13") (pinfunction "13_13") (pintype "passive"))
    )
    (net (code "215") (name "unconnected-(JP6-Pad14)") (class "Default")
      (node (ref "JP6") (pin "14") (pinfunction "14_14") (pintype "passive"))
    )
    (net (code "216") (name "unconnected-(JP6-Pad15)") (class "Default")
      (node (ref "JP6") (pin "15") (pinfunction "15_15") (pintype "passive"))
    )
    (net (code "217") (name "unconnected-(JP6-Pad16)") (class "Default")
      (node (ref "JP6") (pin "16") (pinfunction "16_16") (pintype "passive"))
    )
    (net (code "218") (name "unconnected-(JP6-Pad17)") (class "Default")
      (node (ref "JP6") (pin "17") (pinfunction "17_17") (pintype "passive"))
    )
    (net (code "219") (name "unconnected-(JP6-Pad18)") (class "Default")
      (node (ref "JP6") (pin "18") (pinfunction "18_18") (pintype "passive"))
    )
    (net (code "220") (name "unconnected-(JP6-Pad19)") (class "Default")
      (node (ref "JP6") (pin "19") (pinfunction "19_19") (pintype "passive"))
    )
    (net (code "221") (name "unconnected-(JP6-Pad20)") (class "Default")
      (node (ref "JP6") (pin "20") (pinfunction "20_20") (pintype "passive"))
    )
    (net (code "222") (name "unconnected-(JP6-Pad21)") (class "Default")
      (node (ref "JP6") (pin "21") (pinfunction "21_21") (pintype "passive"))
    )
    (net (code "223") (name "unconnected-(JP6-Pad22)") (class "Default")
      (node (ref "JP6") (pin "22") (pinfunction "22_22") (pintype "passive"))
    )
    (net (code "224") (name "unconnected-(JP6-Pad23)") (class "Default")
      (node (ref "JP6") (pin "23") (pinfunction "23_23") (pintype "passive"))
    )
    (net (code "225") (name "unconnected-(JP6-Pad24)") (class "Default")
      (node (ref "JP6") (pin "24") (pinfunction "24_24") (pintype "passive"))
    )
    (net (code "226") (name "unconnected-(X1P-S-Pad23)") (class "Default")
      (node (ref "X1") (pin "23") (pinfunction "S_23") (pintype "passive"))
    )
    (net (code "227") (name "unconnected-(X1Q-S-Pad24)") (class "Default")
      (node (ref "X1") (pin "24") (pinfunction "S_24") (pintype "passive"))
    )
    (net (code "228") (name "unconnected-(X1R-S-Pad25)") (class "Default")
      (node (ref "X1") (pin "25") (pinfunction "S_25") (pintype "passive"))
    )
    (net (code "229") (name "unconnected-(X1S-S-Pad26)") (class "Default")
      (node (ref "X1") (pin "26") (pinfunction "S_26") (pintype "passive"))
    )
  )
)
